# WM1302_915_SPI_without_SX1262_SKY66420_v.net
KiCad netlist of a schematic drawn in EAGLE
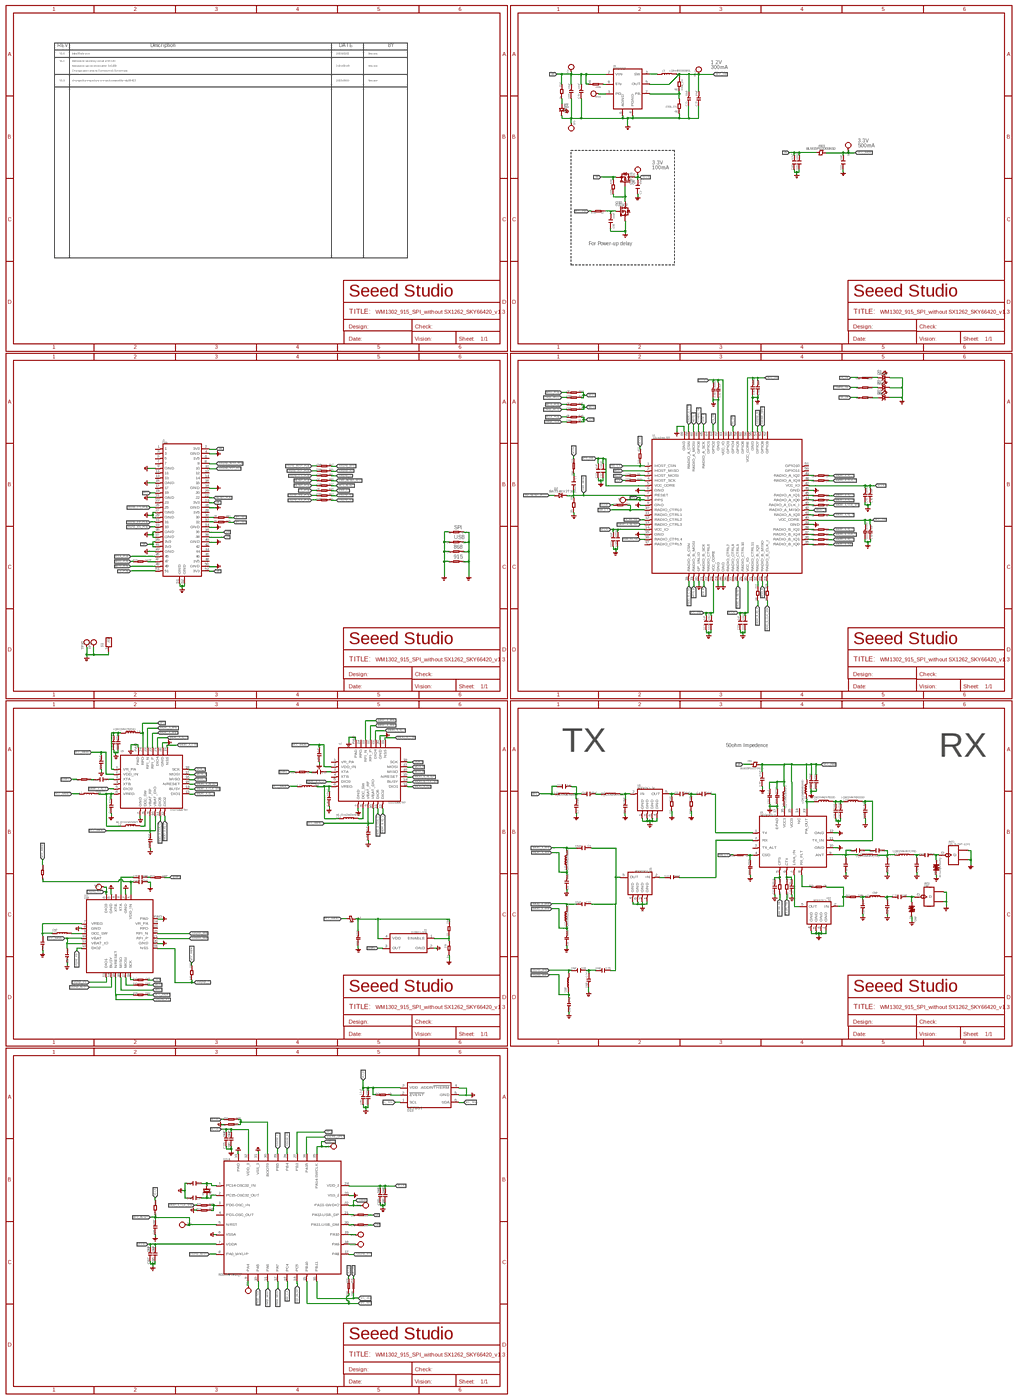
[diagram p0: schematic, sheet 1, overview]
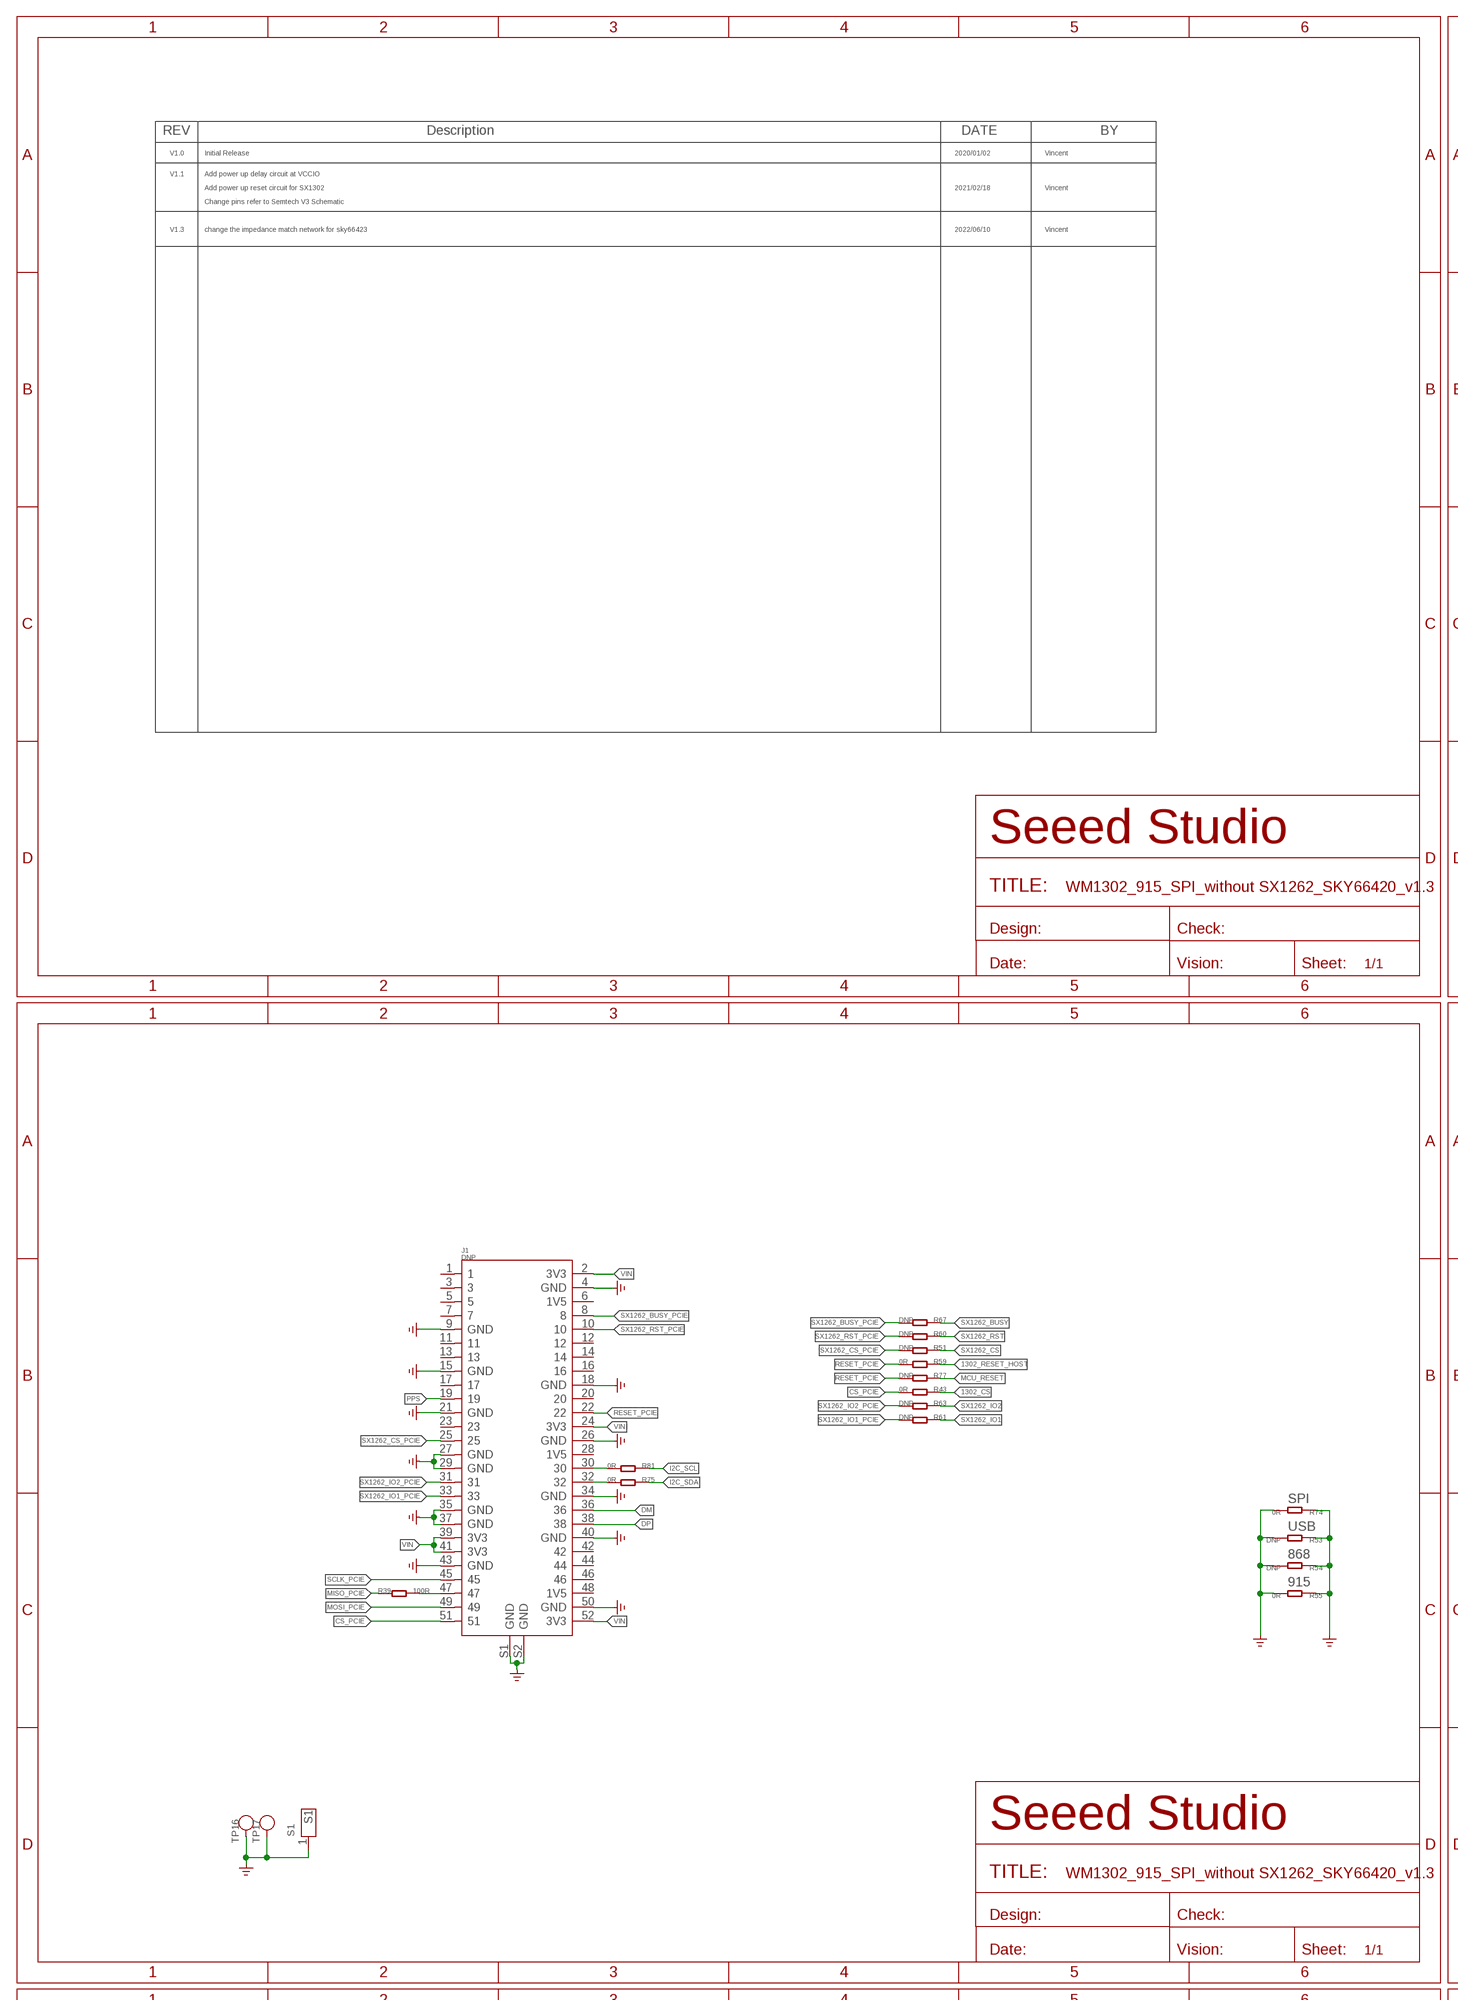
[diagram p1: schematic, sheet 1, part 1 of 4]
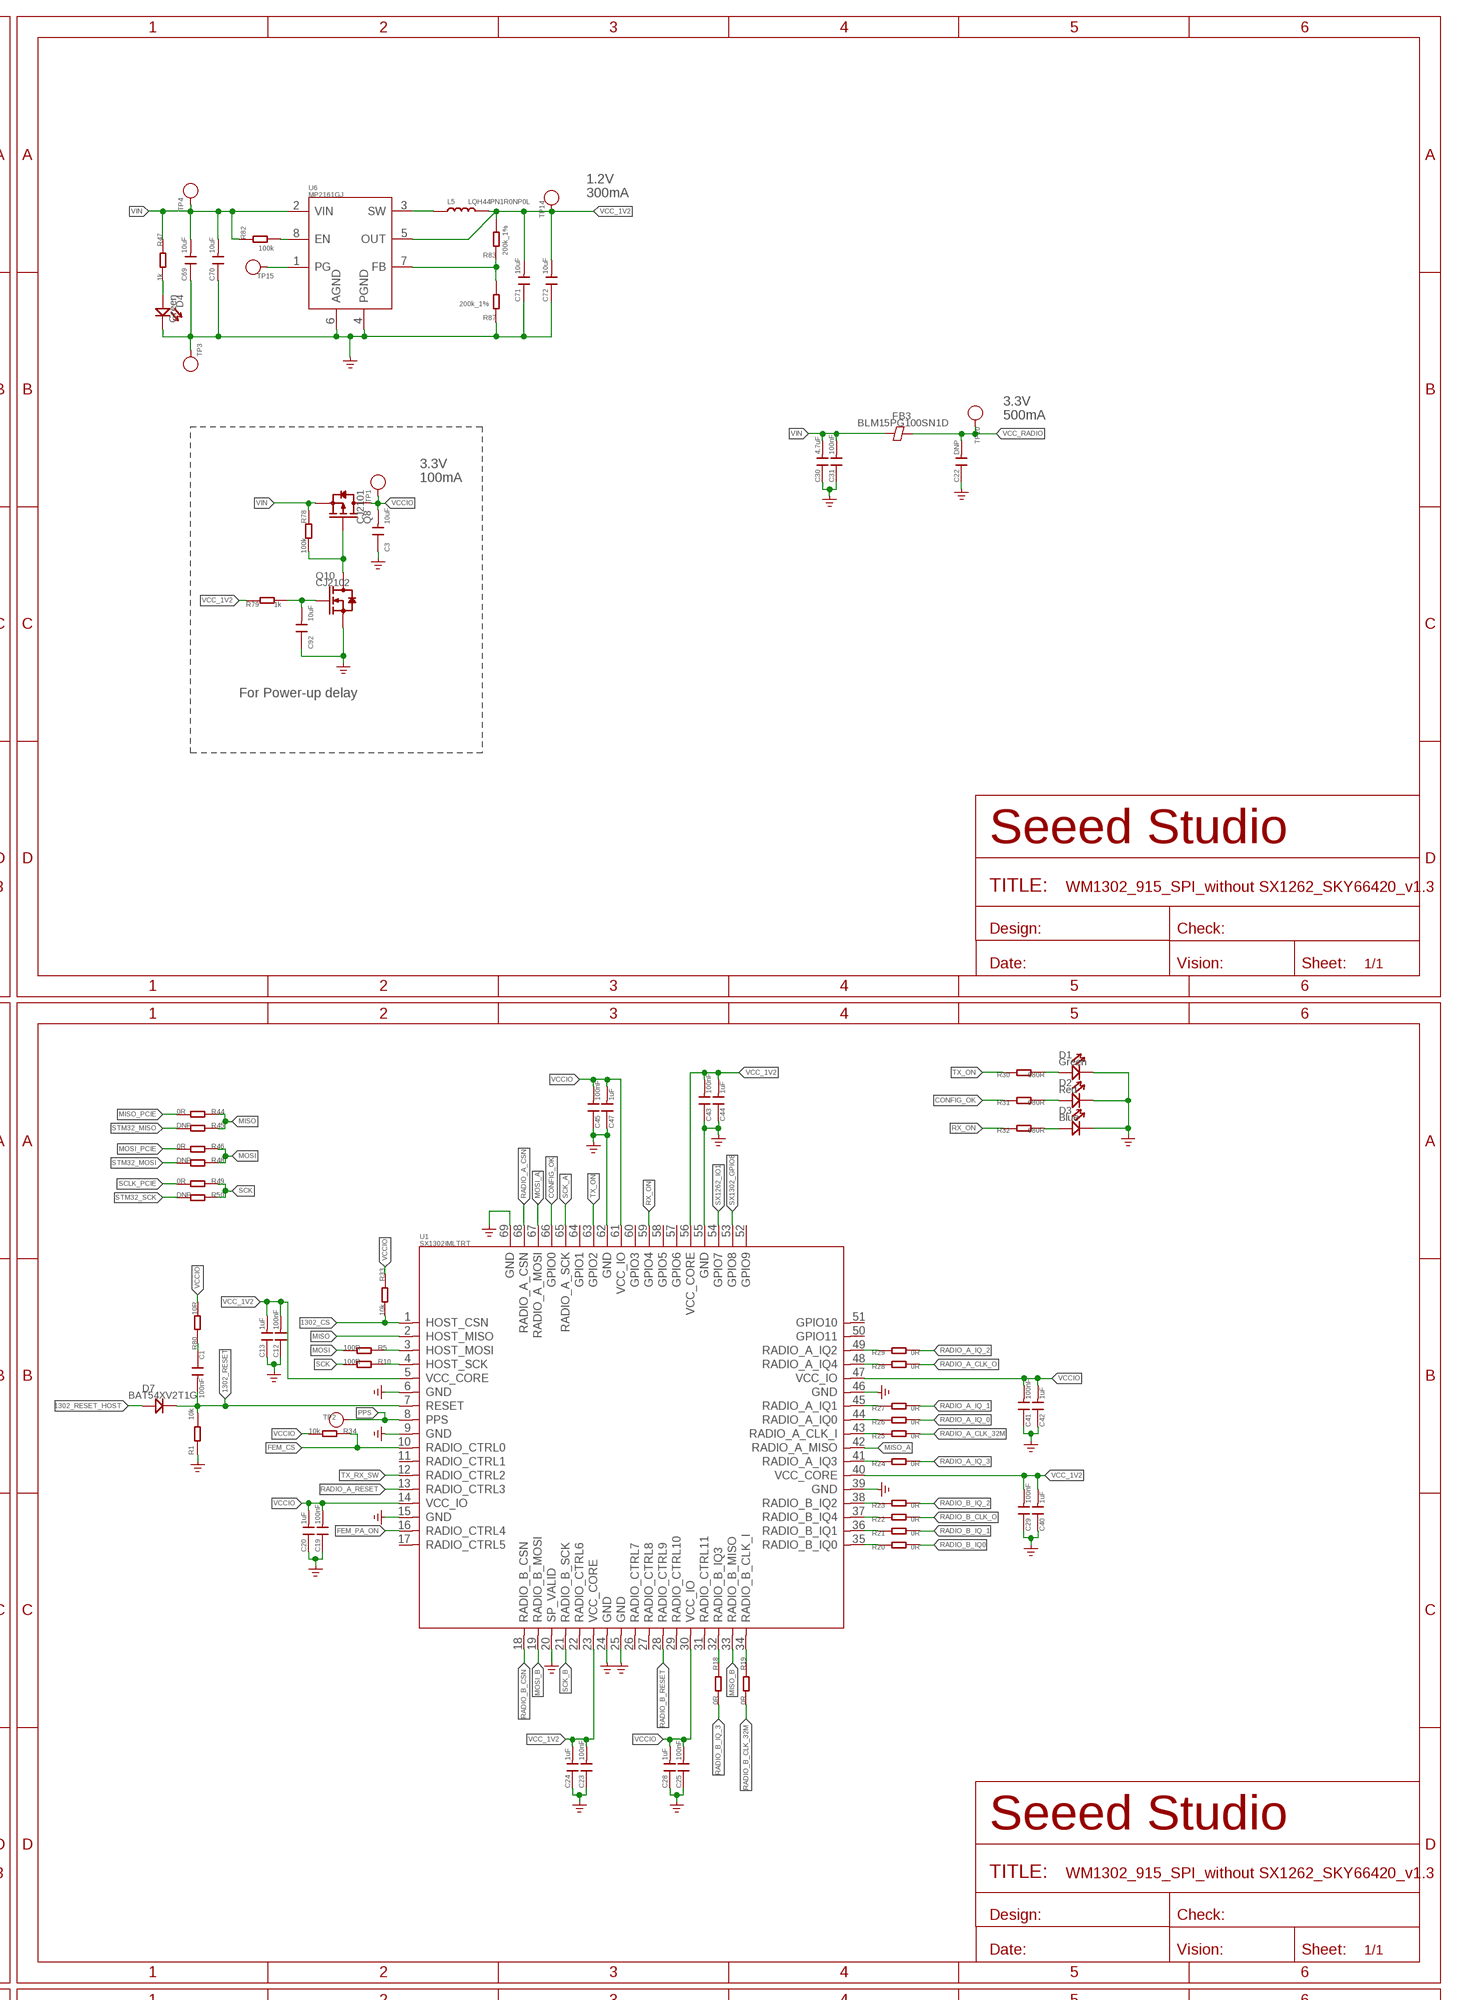
[diagram p2: schematic, sheet 1, part 2 of 4]
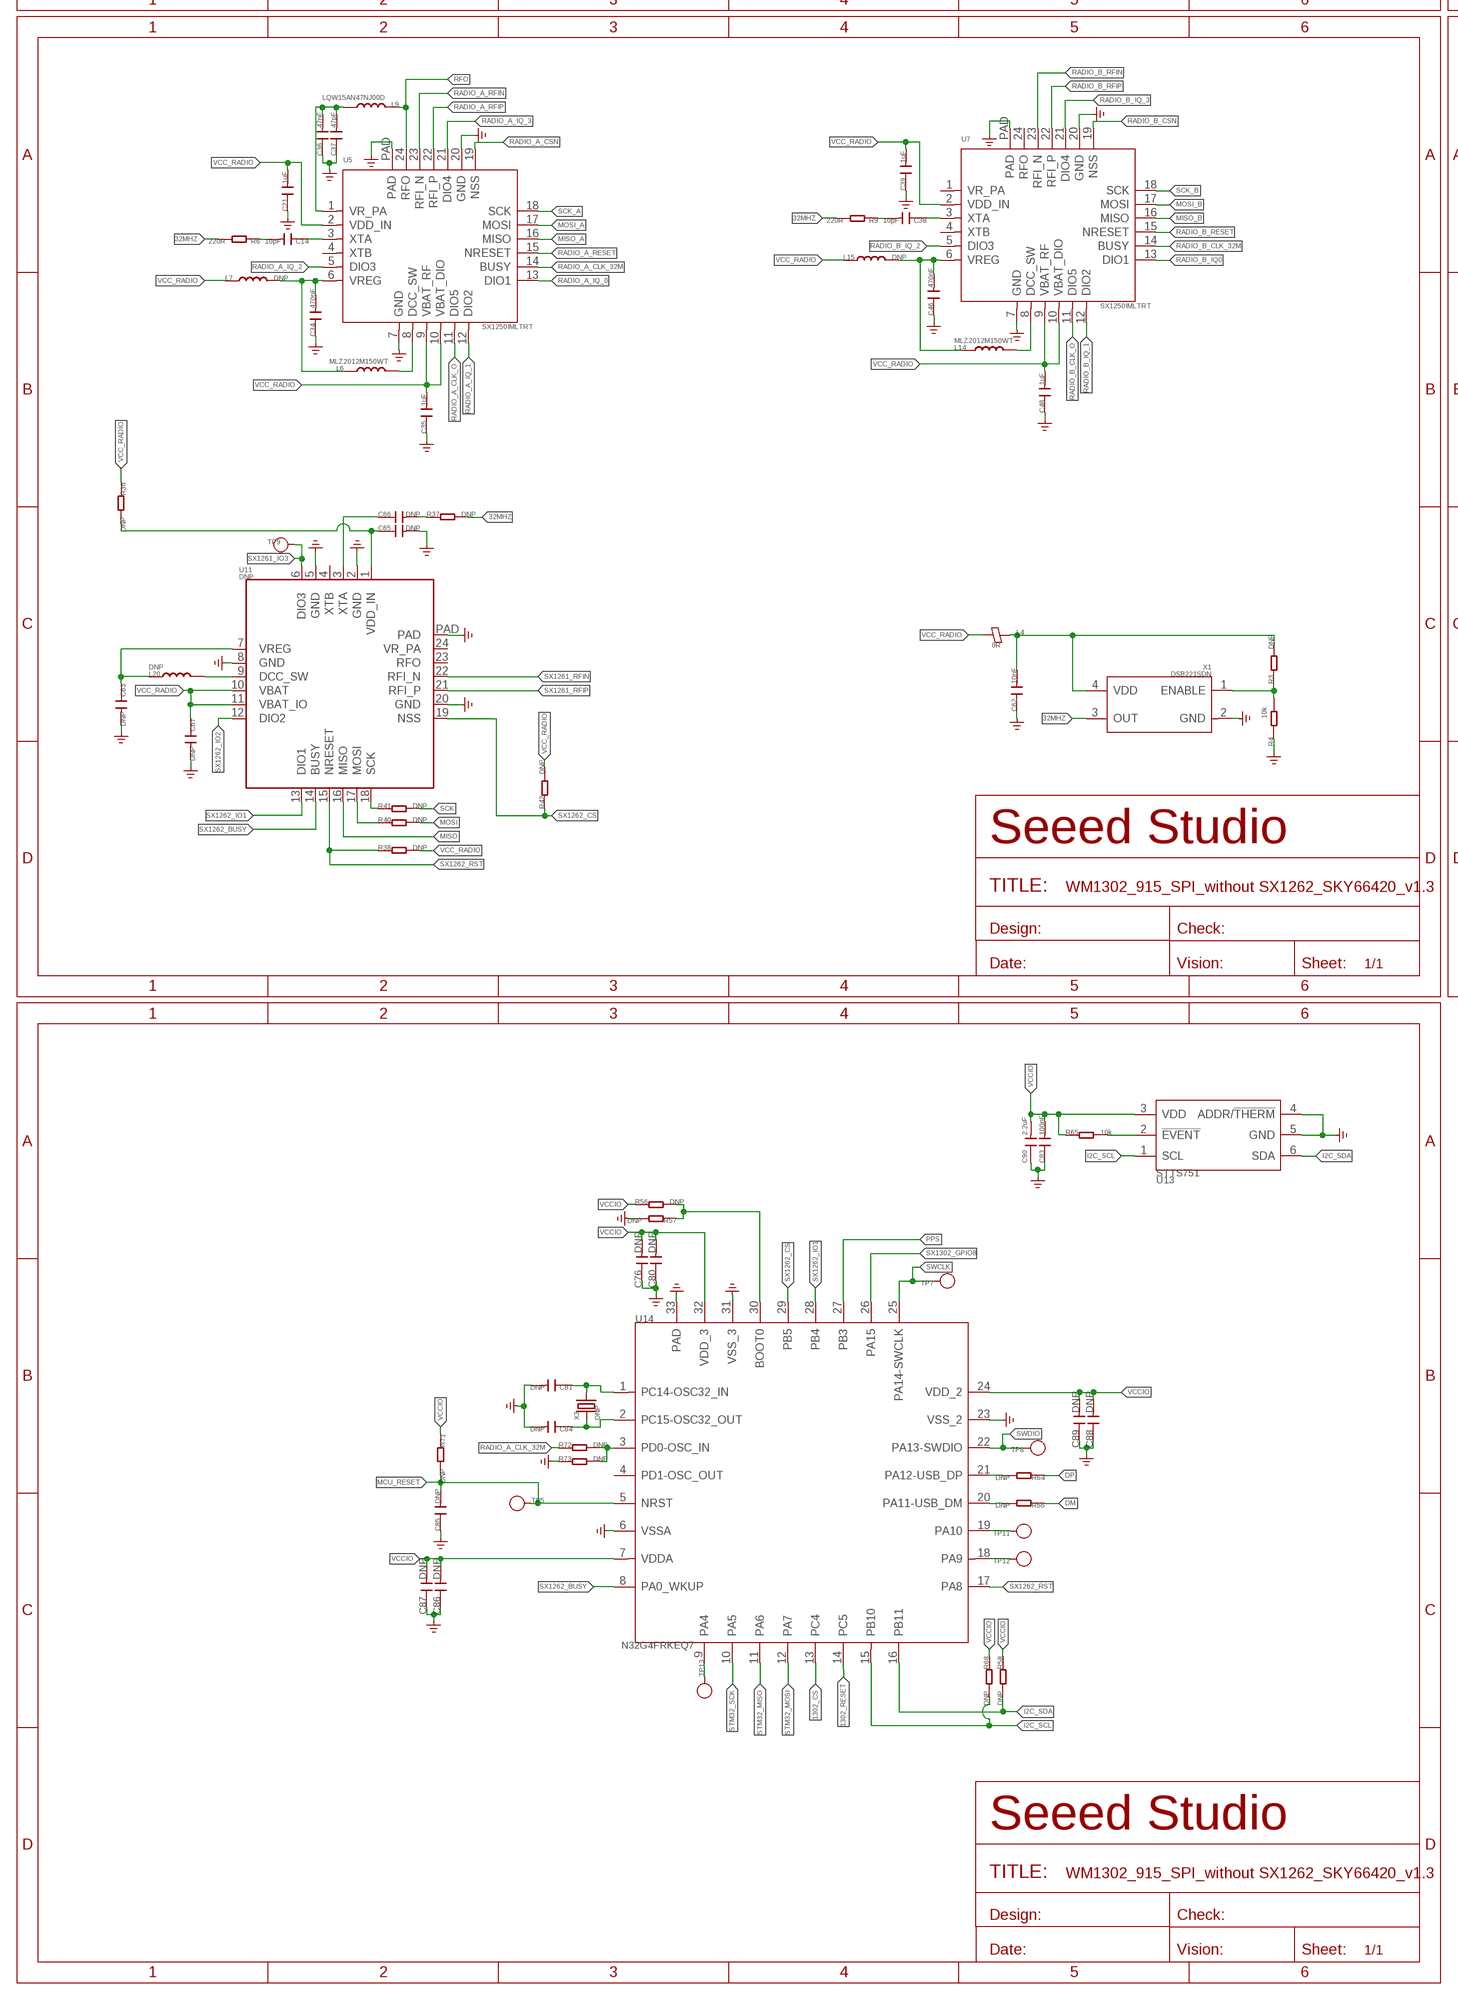
[diagram p3: schematic, sheet 1, part 3 of 4]
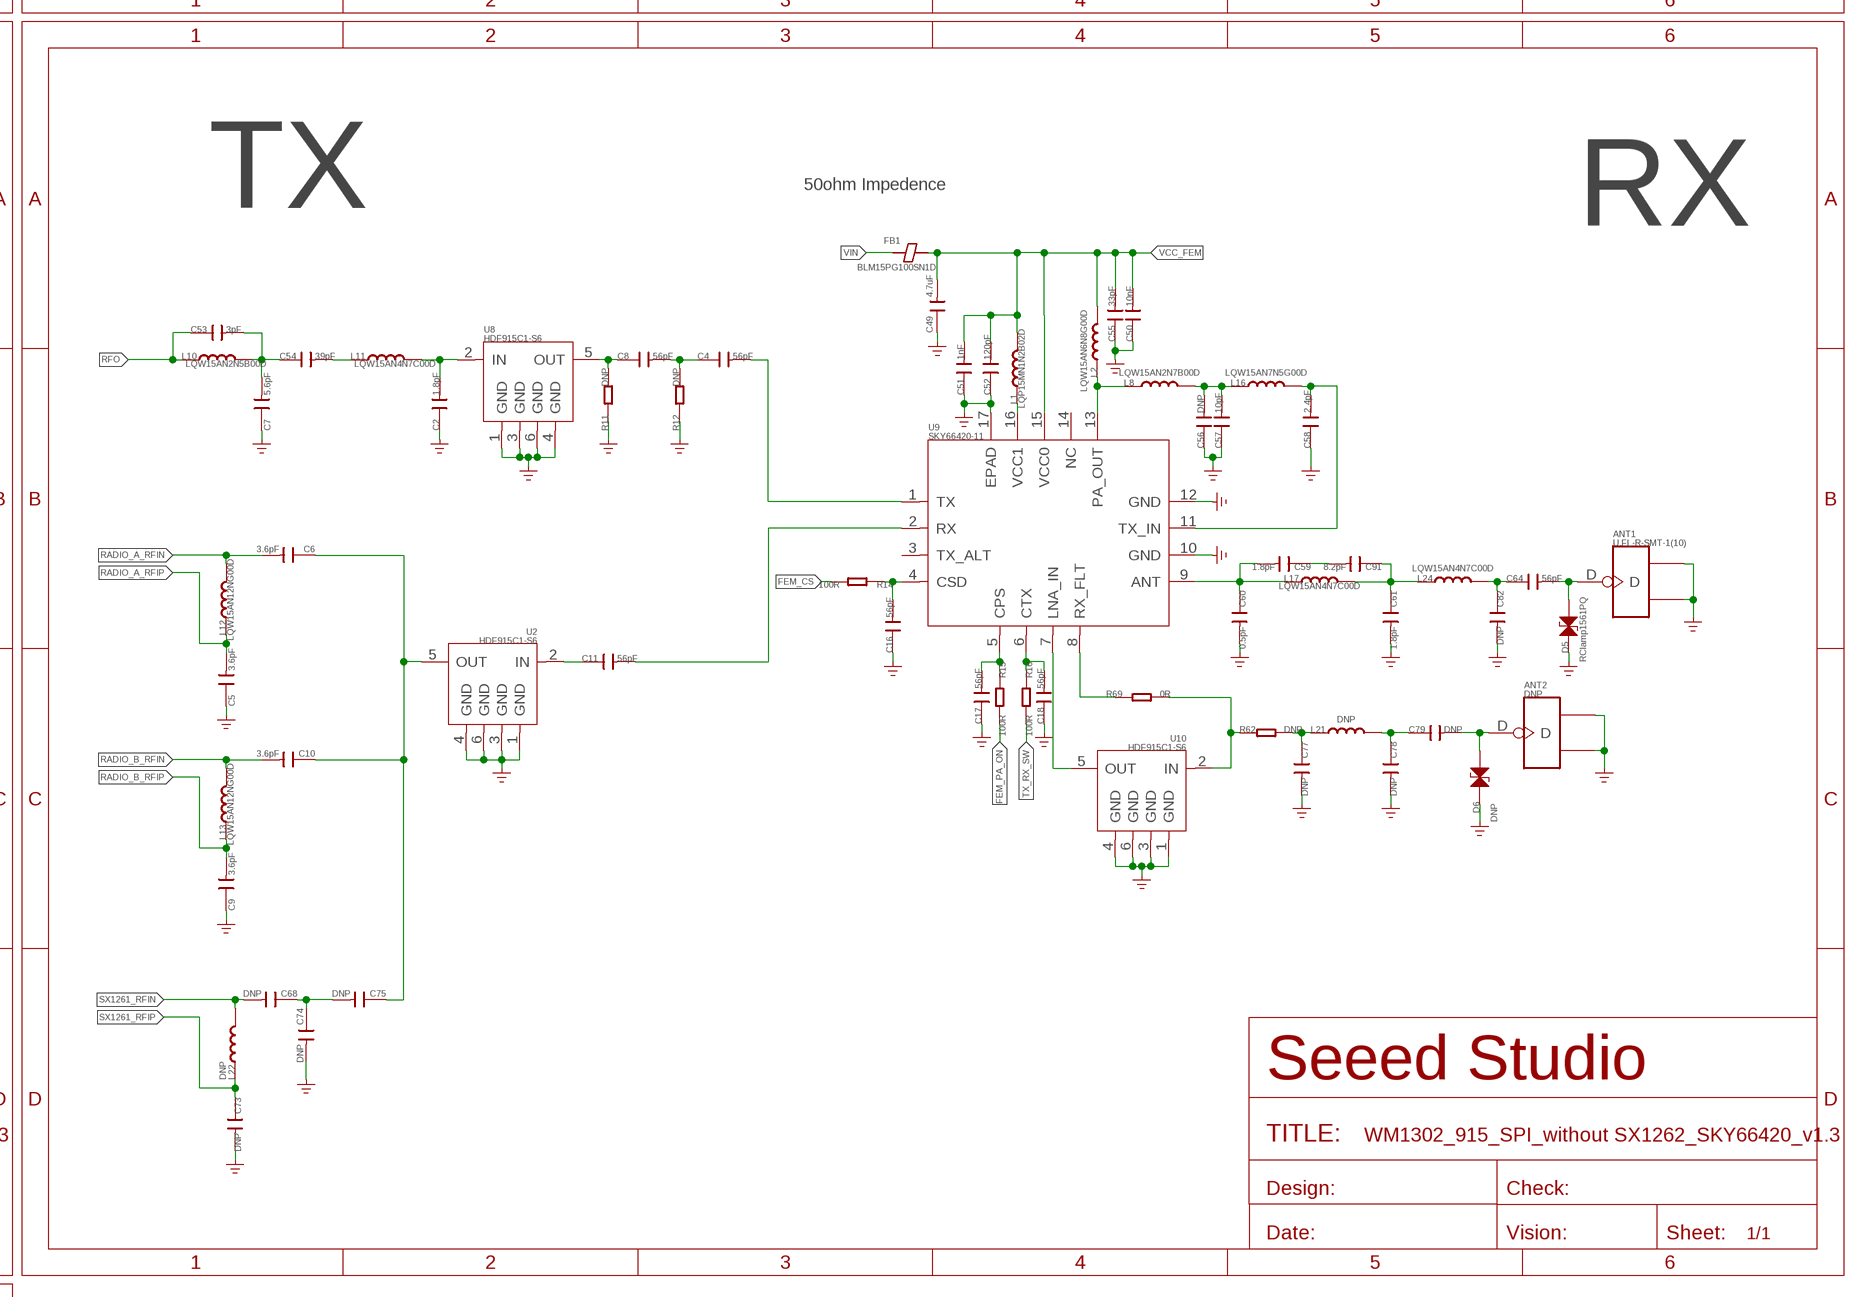
[diagram p4: schematic, sheet 1, part 4 of 4]

(export (version "E")
  (design (tool "Eeschema 10.0.6"))
  (components
    (comp (ref "ANT1")
      (value "U.FL-R-SMT-1(10)")
      (footprint "eagle-import:U-FL3P-SMD-2.6X2.6X1.0MM")
      (fields (field (name "SPICEPREFIX") "J"))
      (libsource (lib "eagle-import") (part "ANTENNA-U-FL-320110048"))
    )
    (comp (ref "ANT2")
      (value "DNP")
      (footprint "eagle-import:U-FL3P-SMD-2.6X2.6X1.0MM")
      (fields (field (name "SPICEPREFIX") "J"))
      (libsource (lib "eagle-import") (part "ANTENNA-U-FL-320110048"))
    )
    (comp (ref "C1")
      (value "100nF")
      (footprint "eagle-import:C0402")
      (libsource (lib "eagle-import") (part "C-0402"))
    )
    (comp (ref "C2")
      (value "1.8pF")
      (footprint "eagle-import:C0402")
      (libsource (lib "eagle-import") (part "C-0402"))
    )
    (comp (ref "C3")
      (value "10uF")
      (footprint "eagle-import:C0603")
      (libsource (lib "eagle-import") (part "C-0603"))
    )
    (comp (ref "C4")
      (value "56pF")
      (footprint "eagle-import:C0402")
      (libsource (lib "eagle-import") (part "C-0402"))
    )
    (comp (ref "C5")
      (value "3.6pF")
      (footprint "eagle-import:C0402")
      (libsource (lib "eagle-import") (part "C-0402"))
    )
    (comp (ref "C6")
      (value "3.6pF")
      (footprint "eagle-import:C0402")
      (libsource (lib "eagle-import") (part "C-0402"))
    )
    (comp (ref "C7")
      (value "5.6pF")
      (footprint "eagle-import:C0402")
      (libsource (lib "eagle-import") (part "C-0402"))
    )
    (comp (ref "C8")
      (value "56pF")
      (footprint "eagle-import:C0402")
      (libsource (lib "eagle-import") (part "C-0402"))
    )
    (comp (ref "C9")
      (value "3.6pF")
      (footprint "eagle-import:C0402")
      (libsource (lib "eagle-import") (part "C-0402"))
    )
    (comp (ref "C10")
      (value "3.6pF")
      (footprint "eagle-import:C0402")
      (libsource (lib "eagle-import") (part "C-0402"))
    )
    (comp (ref "C11")
      (value "56pF")
      (footprint "eagle-import:C0402")
      (libsource (lib "eagle-import") (part "C-0402"))
    )
    (comp (ref "C12")
      (value "100nF")
      (footprint "eagle-import:C0402")
      (libsource (lib "eagle-import") (part "C-0402"))
    )
    (comp (ref "C13")
      (value "1uF")
      (footprint "eagle-import:C0402")
      (libsource (lib "eagle-import") (part "C-0402"))
    )
    (comp (ref "C14")
      (value "10pF")
      (footprint "eagle-import:C0402")
      (libsource (lib "eagle-import") (part "C-0402"))
    )
    (comp (ref "C16")
      (value "56pF")
      (footprint "eagle-import:C0402")
      (libsource (lib "eagle-import") (part "C-0402"))
    )
    (comp (ref "C17")
      (value "56pF")
      (footprint "eagle-import:C0402")
      (libsource (lib "eagle-import") (part "C-0402"))
    )
    (comp (ref "C18")
      (value "56pF")
      (footprint "eagle-import:C0402")
      (libsource (lib "eagle-import") (part "C-0402"))
    )
    (comp (ref "C19")
      (value "100nF")
      (footprint "eagle-import:C0402")
      (libsource (lib "eagle-import") (part "C-0402"))
    )
    (comp (ref "C20")
      (value "1uF")
      (footprint "eagle-import:C0402")
      (libsource (lib "eagle-import") (part "C-0402"))
    )
    (comp (ref "C21")
      (value "1uF")
      (footprint "eagle-import:C0402")
      (libsource (lib "eagle-import") (part "C-0402"))
    )
    (comp (ref "C22")
      (value "DNP")
      (footprint "eagle-import:C0402")
      (libsource (lib "eagle-import") (part "C-0402"))
    )
    (comp (ref "C23")
      (value "100nF")
      (footprint "eagle-import:C0402")
      (libsource (lib "eagle-import") (part "C-0402"))
    )
    (comp (ref "C24")
      (value "1uF")
      (footprint "eagle-import:C0402")
      (libsource (lib "eagle-import") (part "C-0402"))
    )
    (comp (ref "C25")
      (value "100nF")
      (footprint "eagle-import:C0402")
      (libsource (lib "eagle-import") (part "C-0402"))
    )
    (comp (ref "C28")
      (value "1uF")
      (footprint "eagle-import:C0402")
      (libsource (lib "eagle-import") (part "C-0402"))
    )
    (comp (ref "C29")
      (value "100nF")
      (footprint "eagle-import:C0402")
      (libsource (lib "eagle-import") (part "C-0402"))
    )
    (comp (ref "C30")
      (value "4.7uF")
      (footprint "eagle-import:C0603")
      (libsource (lib "eagle-import") (part "C-0603"))
    )
    (comp (ref "C31")
      (value "100nF")
      (footprint "eagle-import:C0402")
      (libsource (lib "eagle-import") (part "C-0402"))
    )
    (comp (ref "C34")
      (value "470nF")
      (footprint "eagle-import:C0402")
      (libsource (lib "eagle-import") (part "C-0402"))
    )
    (comp (ref "C35")
      (value "1uF")
      (footprint "eagle-import:C0402")
      (libsource (lib "eagle-import") (part "C-0402"))
    )
    (comp (ref "C36")
      (value "47nF")
      (footprint "eagle-import:C0402")
      (libsource (lib "eagle-import") (part "C-0402"))
    )
    (comp (ref "C37")
      (value "47pF")
      (footprint "eagle-import:C0402")
      (libsource (lib "eagle-import") (part "C-0402"))
    )
    (comp (ref "C38")
      (value "10pF")
      (footprint "eagle-import:C0402")
      (libsource (lib "eagle-import") (part "C-0402"))
    )
    (comp (ref "C39")
      (value "1uF")
      (footprint "eagle-import:C0402")
      (libsource (lib "eagle-import") (part "C-0402"))
    )
    (comp (ref "C40")
      (value "1uF")
      (footprint "eagle-import:C0402")
      (libsource (lib "eagle-import") (part "C-0402"))
    )
    (comp (ref "C41")
      (value "100nF")
      (footprint "eagle-import:C0402")
      (libsource (lib "eagle-import") (part "C-0402"))
    )
    (comp (ref "C42")
      (value "1uF")
      (footprint "eagle-import:C0402")
      (libsource (lib "eagle-import") (part "C-0402"))
    )
    (comp (ref "C43")
      (value "100nF")
      (footprint "eagle-import:C0402")
      (libsource (lib "eagle-import") (part "C-0402"))
    )
    (comp (ref "C44")
      (value "1uF")
      (footprint "eagle-import:C0402")
      (libsource (lib "eagle-import") (part "C-0402"))
    )
    (comp (ref "C45")
      (value "100nF")
      (footprint "eagle-import:C0402")
      (libsource (lib "eagle-import") (part "C-0402"))
    )
    (comp (ref "C46")
      (value "470nF")
      (footprint "eagle-import:C0402")
      (libsource (lib "eagle-import") (part "C-0402"))
    )
    (comp (ref "C47")
      (value "1uF")
      (footprint "eagle-import:C0402")
      (libsource (lib "eagle-import") (part "C-0402"))
    )
    (comp (ref "C48")
      (value "1uF")
      (footprint "eagle-import:C0402")
      (libsource (lib "eagle-import") (part "C-0402"))
    )
    (comp (ref "C49")
      (value "4.7uF")
      (footprint "eagle-import:C0603")
      (libsource (lib "eagle-import") (part "C-0603"))
    )
    (comp (ref "C50")
      (value "10nF")
      (footprint "eagle-import:C0402")
      (libsource (lib "eagle-import") (part "C-0402"))
    )
    (comp (ref "C51")
      (value "1nF")
      (footprint "eagle-import:C0402")
      (libsource (lib "eagle-import") (part "C-0402"))
    )
    (comp (ref "C52")
      (value "120pF")
      (footprint "eagle-import:C0402")
      (libsource (lib "eagle-import") (part "C-0402"))
    )
    (comp (ref "C53")
      (value "3pF")
      (footprint "eagle-import:C0402")
      (libsource (lib "eagle-import") (part "C-0402"))
    )
    (comp (ref "C54")
      (value "39pF")
      (footprint "eagle-import:C0402")
      (libsource (lib "eagle-import") (part "C-0402"))
    )
    (comp (ref "C55")
      (value "33pF")
      (footprint "eagle-import:C0402")
      (fields (field (name "SPICEPREFIX") "C"))
      (libsource (lib "eagle-import") (part "C-0402"))
    )
    (comp (ref "C56")
      (value "DNP")
      (footprint "eagle-import:C0402")
      (libsource (lib "eagle-import") (part "C-0402"))
    )
    (comp (ref "C57")
      (value "10pF")
      (footprint "eagle-import:C0402")
      (libsource (lib "eagle-import") (part "C-0402"))
    )
    (comp (ref "C58")
      (value "2.4pF")
      (footprint "eagle-import:C0402")
      (libsource (lib "eagle-import") (part "C-0402"))
    )
    (comp (ref "C59")
      (value "1.8pF")
      (footprint "eagle-import:C0402")
      (libsource (lib "eagle-import") (part "C-0402"))
    )
    (comp (ref "C60")
      (value "0.5pF")
      (footprint "eagle-import:C0402")
      (libsource (lib "eagle-import") (part "C-0402"))
    )
    (comp (ref "C61")
      (value "1.8pF")
      (footprint "eagle-import:C0402")
      (libsource (lib "eagle-import") (part "C-0402"))
    )
    (comp (ref "C62")
      (value "10nF")
      (footprint "eagle-import:C0402")
      (libsource (lib "eagle-import") (part "C-0402"))
    )
    (comp (ref "C63")
      (value "DNP")
      (footprint "eagle-import:C0402")
      (libsource (lib "eagle-import") (part "C-0402"))
    )
    (comp (ref "C64")
      (value "56pF")
      (footprint "eagle-import:C0402")
      (libsource (lib "eagle-import") (part "C-0402"))
    )
    (comp (ref "C65")
      (value "DNP")
      (footprint "eagle-import:C0402")
      (libsource (lib "eagle-import") (part "C-0402"))
    )
    (comp (ref "C66")
      (value "DNP")
      (footprint "eagle-import:C0402")
      (libsource (lib "eagle-import") (part "C-0402"))
    )
    (comp (ref "C67")
      (value "DNP")
      (footprint "eagle-import:C0402")
      (libsource (lib "eagle-import") (part "C-0402"))
    )
    (comp (ref "C68")
      (value "DNP")
      (footprint "eagle-import:C0402")
      (libsource (lib "eagle-import") (part "C-0402"))
    )
    (comp (ref "C69")
      (value "10uF")
      (footprint "eagle-import:C0805")
      (libsource (lib "eagle-import") (part "CAP-0805"))
    )
    (comp (ref "C70")
      (value "10uF")
      (footprint "eagle-import:C0805")
      (libsource (lib "eagle-import") (part "CAP-0805"))
    )
    (comp (ref "C71")
      (value "10uF")
      (footprint "eagle-import:C0805")
      (libsource (lib "eagle-import") (part "CAP-0805"))
    )
    (comp (ref "C72")
      (value "10uF")
      (footprint "eagle-import:C0805")
      (libsource (lib "eagle-import") (part "CAP-0805"))
    )
    (comp (ref "C73")
      (value "DNP")
      (footprint "eagle-import:C0402")
      (libsource (lib "eagle-import") (part "C-0402"))
    )
    (comp (ref "C74")
      (value "DNP")
      (footprint "eagle-import:C0402")
      (libsource (lib "eagle-import") (part "C-0402"))
    )
    (comp (ref "C75")
      (value "DNP")
      (footprint "eagle-import:C0402")
      (libsource (lib "eagle-import") (part "C-0402"))
    )
    (comp (ref "C76")
      (value "DNP")
      (footprint "eagle-import:C0402")
      (libsource (lib "eagle-import") (part "C-0402"))
    )
    (comp (ref "C77")
      (value "DNP")
      (footprint "eagle-import:C0402")
      (libsource (lib "eagle-import") (part "C-0402"))
    )
    (comp (ref "C78")
      (value "DNP")
      (footprint "eagle-import:C0402")
      (libsource (lib "eagle-import") (part "C-0402"))
    )
    (comp (ref "C79")
      (value "DNP")
      (footprint "eagle-import:C0402")
      (libsource (lib "eagle-import") (part "C-0402"))
    )
    (comp (ref "C80")
      (value "DNP")
      (footprint "eagle-import:C0402")
      (libsource (lib "eagle-import") (part "C-0402"))
    )
    (comp (ref "C81")
      (value "DNP")
      (footprint "eagle-import:C0402")
      (libsource (lib "eagle-import") (part "C-0402"))
    )
    (comp (ref "C82")
      (value "DNP")
      (footprint "eagle-import:C0402")
      (libsource (lib "eagle-import") (part "C-0402"))
    )
    (comp (ref "C83")
      (value "100nF")
      (footprint "eagle-import:C0402")
      (libsource (lib "eagle-import") (part "C-0402"))
    )
    (comp (ref "C84")
      (value "DNP")
      (footprint "eagle-import:C0402")
      (libsource (lib "eagle-import") (part "C-0402"))
    )
    (comp (ref "C85")
      (value "DNP")
      (footprint "eagle-import:C0402")
      (libsource (lib "eagle-import") (part "C-0402"))
    )
    (comp (ref "C86")
      (value "DNP")
      (footprint "eagle-import:C0402")
      (libsource (lib "eagle-import") (part "C-0402"))
    )
    (comp (ref "C87")
      (value "DNP")
      (footprint "eagle-import:C0402")
      (libsource (lib "eagle-import") (part "C-0402"))
    )
    (comp (ref "C88")
      (value "DNP")
      (footprint "eagle-import:C0402")
      (libsource (lib "eagle-import") (part "C-0402"))
    )
    (comp (ref "C89")
      (value "DNP")
      (footprint "eagle-import:C0402")
      (libsource (lib "eagle-import") (part "C-0402"))
    )
    (comp (ref "C90")
      (value "2.2uF")
      (footprint "eagle-import:C0603")
      (libsource (lib "eagle-import") (part "C-0603"))
    )
    (comp (ref "C91")
      (value "8.2pF")
      (footprint "eagle-import:C0402")
      (libsource (lib "eagle-import") (part "C-0402"))
    )
    (comp (ref "C92")
      (value "10uF")
      (footprint "eagle-import:C0603")
      (libsource (lib "eagle-import") (part "C-0603"))
    )
    (comp (ref "D1")
      (value "Green")
      (footprint "eagle-import:LED-0402")
      (libsource (lib "eagle-import") (part "LED-0402"))
    )
    (comp (ref "D2")
      (value "Red")
      (footprint "eagle-import:LED-0402")
      (libsource (lib "eagle-import") (part "LED-0402"))
    )
    (comp (ref "D3")
      (value "Blue")
      (footprint "eagle-import:LED-0402")
      (libsource (lib "eagle-import") (part "LED-0402"))
    )
    (comp (ref "D4")
      (value "Green")
      (footprint "eagle-import:LED-0402")
      (libsource (lib "eagle-import") (part "LED-0402"))
    )
    (comp (ref "D5")
      (value "RClamp1561PQ")
      (footprint "eagle-import:ESD-0402")
      (fields (field (name "SPICEPREFIX") "D"))
      (libsource (lib "eagle-import") (part "D-ESD-2P-DOUBLE-0402"))
    )
    (comp (ref "D6")
      (value "DNP")
      (footprint "eagle-import:ESD-0402")
      (libsource (lib "eagle-import") (part "D-ESD-2P-DOUBLE-0402"))
    )
    (comp (ref "D7")
      (value "BAT54XV2T1G")
      (footprint "eagle-import:SOD-523")
      (libsource (lib "eagle-import") (part "DIODE'0603'"))
    )
    (comp (ref "FB1")
      (value "BLM15PG100SN1D")
      (footprint "eagle-import:F0402")
      (libsource (lib "eagle-import") (part "FERRITE-BEAD-0402"))
    )
    (comp (ref "FB3")
      (value "BLM15PG100SN1D")
      (footprint "eagle-import:F0402")
      (libsource (lib "eagle-import") (part "FERRITE-BEAD-0402"))
    )
    (comp (ref "J1")
      (value "DNP")
      (footprint "eagle-import:PCIE52P-0.8-50.95X30MM")
      (libsource (lib "eagle-import") (part "MOUDLE-FULL-MINI-PCIE"))
    )
    (comp (ref "L1")
      (value "LQP15MN1N2B02D")
      (footprint "eagle-import:L0402")
      (libsource (lib "eagle-import") (part "L-0402"))
    )
    (comp (ref "L2")
      (value "LQW15AN6N8G00D")
      (footprint "eagle-import:L0402")
      (libsource (lib "eagle-import") (part "L-0402"))
    )
    (comp (ref "L4")
      (value "0R")
      (footprint "eagle-import:F0603")
      (libsource (lib "eagle-import") (part "FERRITE-BEAD-0603"))
    )
    (comp (ref "L5")
      (value "LQH44PN1R0NP0L")
      (footprint "eagle-import:L4.4X3.0MM")
      (libsource (lib "eagle-import") (part "INDUCTOR-4430"))
    )
    (comp (ref "L6")
      (value "MLZ2012M150WT")
      (footprint "eagle-import:L202012")
      (libsource (lib "eagle-import") (part "INDUCTOR-SPH202012"))
    )
    (comp (ref "L7")
      (value "DNP")
      (footprint "eagle-import:L0402")
      (libsource (lib "eagle-import") (part "L-0402"))
    )
    (comp (ref "L8")
      (value "LQW15AN2N7B00D")
      (footprint "eagle-import:L0402")
      (libsource (lib "eagle-import") (part "L-0402"))
    )
    (comp (ref "L9")
      (value "LQW15AN47NJ00D")
      (footprint "eagle-import:L0402")
      (libsource (lib "eagle-import") (part "L-0402"))
    )
    (comp (ref "L10")
      (value "LQW15AN2N5B00D")
      (footprint "eagle-import:L0402")
      (libsource (lib "eagle-import") (part "L-0402"))
    )
    (comp (ref "L11")
      (value "LQW15AN4N7C00D")
      (footprint "eagle-import:L0402")
      (libsource (lib "eagle-import") (part "L-0402"))
    )
    (comp (ref "L12")
      (value "LQW15AN12NG00D")
      (footprint "eagle-import:L0402")
      (libsource (lib "eagle-import") (part "L-0402"))
    )
    (comp (ref "L13")
      (value "LQW15AN12NG00D")
      (footprint "eagle-import:L0402")
      (libsource (lib "eagle-import") (part "L-0402"))
    )
    (comp (ref "L14")
      (value "MLZ2012M150WT")
      (footprint "eagle-import:L202012")
      (libsource (lib "eagle-import") (part "INDUCTOR-SPH202012"))
    )
    (comp (ref "L15")
      (value "DNP")
      (footprint "eagle-import:L0402")
      (libsource (lib "eagle-import") (part "L-0402"))
    )
    (comp (ref "L16")
      (value "LQW15AN7N5G00D")
      (footprint "eagle-import:L0402")
      (libsource (lib "eagle-import") (part "L-0402"))
    )
    (comp (ref "L17")
      (value "LQW15AN4N7C00D")
      (footprint "eagle-import:L0402")
      (libsource (lib "eagle-import") (part "L-0402"))
    )
    (comp (ref "L20")
      (value "DNP")
      (footprint "eagle-import:L202012")
      (libsource (lib "eagle-import") (part "INDUCTOR-SPH202012"))
    )
    (comp (ref "L21")
      (value "DNP")
      (footprint "eagle-import:L0402")
      (libsource (lib "eagle-import") (part "L-0402"))
    )
    (comp (ref "L22")
      (value "DNP")
      (footprint "eagle-import:L0402")
      (libsource (lib "eagle-import") (part "L-0402"))
    )
    (comp (ref "L24")
      (value "LQW15AN4N7C00D")
      (footprint "eagle-import:L0402")
      (libsource (lib "eagle-import") (part "L-0402"))
    )
    (comp (ref "Q8")
      (value "CJ2101")
      (footprint "eagle-import:SOT-323")
      (libsource (lib "eagle-import") (part "MOSFET-P-SOT323"))
    )
    (comp (ref "Q10")
      (value "CJ2102")
      (footprint "eagle-import:SOT-323")
      (libsource (lib "eagle-import") (part "MOSFET-N-SI1304BDL"))
    )
    (comp (ref "R1")
      (value "10k")
      (footprint "eagle-import:R0402")
      (libsource (lib "eagle-import") (part "R-0402"))
    )
    (comp (ref "R3")
      (value "DNP")
      (footprint "eagle-import:R0402")
      (libsource (lib "eagle-import") (part "R-0402"))
    )
    (comp (ref "R4")
      (value "10k")
      (footprint "eagle-import:R0402")
      (libsource (lib "eagle-import") (part "R-0402"))
    )
    (comp (ref "R5")
      (value "100R")
      (footprint "eagle-import:R0402")
      (libsource (lib "eagle-import") (part "R-0402"))
    )
    (comp (ref "R6")
      (value "220R")
      (footprint "eagle-import:R0402")
      (libsource (lib "eagle-import") (part "R-0402"))
    )
    (comp (ref "R9")
      (value "220R")
      (footprint "eagle-import:R0402")
      (libsource (lib "eagle-import") (part "R-0402"))
    )
    (comp (ref "R10")
      (value "100R")
      (footprint "eagle-import:R0402")
      (libsource (lib "eagle-import") (part "R-0402"))
    )
    (comp (ref "R11")
      (value "DNP")
      (footprint "eagle-import:R0402")
      (libsource (lib "eagle-import") (part "R-0402"))
    )
    (comp (ref "R12")
      (value "DNP")
      (footprint "eagle-import:R0402")
      (libsource (lib "eagle-import") (part "R-0402"))
    )
    (comp (ref "R14")
      (value "100R")
      (footprint "eagle-import:R0402")
      (libsource (lib "eagle-import") (part "R-0402"))
    )
    (comp (ref "R15")
      (value "100R")
      (footprint "eagle-import:R0402")
      (libsource (lib "eagle-import") (part "R-0402"))
    )
    (comp (ref "R16")
      (value "100R")
      (footprint "eagle-import:R0402")
      (libsource (lib "eagle-import") (part "R-0402"))
    )
    (comp (ref "R18")
      (value "0R")
      (footprint "eagle-import:R0402")
      (libsource (lib "eagle-import") (part "R-0402"))
    )
    (comp (ref "R19")
      (value "0R")
      (footprint "eagle-import:R0402")
      (libsource (lib "eagle-import") (part "R-0402"))
    )
    (comp (ref "R20")
      (value "0R")
      (footprint "eagle-import:R0402")
      (libsource (lib "eagle-import") (part "R-0402"))
    )
    (comp (ref "R21")
      (value "0R")
      (footprint "eagle-import:R0402")
      (libsource (lib "eagle-import") (part "R-0402"))
    )
    (comp (ref "R22")
      (value "0R")
      (footprint "eagle-import:R0402")
      (libsource (lib "eagle-import") (part "R-0402"))
    )
    (comp (ref "R23")
      (value "0R")
      (footprint "eagle-import:R0402")
      (libsource (lib "eagle-import") (part "R-0402"))
    )
    (comp (ref "R24")
      (value "0R")
      (footprint "eagle-import:R0402")
      (libsource (lib "eagle-import") (part "R-0402"))
    )
    (comp (ref "R25")
      (value "0R")
      (footprint "eagle-import:R0402")
      (libsource (lib "eagle-import") (part "R-0402"))
    )
    (comp (ref "R26")
      (value "0R")
      (footprint "eagle-import:R0402")
      (libsource (lib "eagle-import") (part "R-0402"))
    )
    (comp (ref "R27")
      (value "0R")
      (footprint "eagle-import:R0402")
      (libsource (lib "eagle-import") (part "R-0402"))
    )
    (comp (ref "R28")
      (value "0R")
      (footprint "eagle-import:R0402")
      (libsource (lib "eagle-import") (part "R-0402"))
    )
    (comp (ref "R29")
      (value "0R")
      (footprint "eagle-import:R0402")
      (libsource (lib "eagle-import") (part "R-0402"))
    )
    (comp (ref "R30")
      (value "680R")
      (footprint "eagle-import:R0402")
      (libsource (lib "eagle-import") (part "R-0402"))
    )
    (comp (ref "R31")
      (value "680R")
      (footprint "eagle-import:R0402")
      (libsource (lib "eagle-import") (part "R-0402"))
    )
    (comp (ref "R32")
      (value "680R")
      (footprint "eagle-import:R0402")
      (libsource (lib "eagle-import") (part "R-0402"))
    )
    (comp (ref "R33")
      (value "10k")
      (footprint "eagle-import:R0402")
      (libsource (lib "eagle-import") (part "R-0402"))
    )
    (comp (ref "R34")
      (value "10k")
      (footprint "eagle-import:R0402")
      (libsource (lib "eagle-import") (part "R-0402"))
    )
    (comp (ref "R36")
      (value "DNP")
      (footprint "eagle-import:R0402")
      (libsource (lib "eagle-import") (part "R-0402"))
    )
    (comp (ref "R37")
      (value "DNP")
      (footprint "eagle-import:R0402")
      (libsource (lib "eagle-import") (part "R-0402"))
    )
    (comp (ref "R38")
      (value "DNP")
      (footprint "eagle-import:R0402")
      (libsource (lib "eagle-import") (part "R-0402"))
    )
    (comp (ref "R39")
      (value "100R")
      (footprint "eagle-import:R0402")
      (libsource (lib "eagle-import") (part "R-0402"))
    )
    (comp (ref "R40")
      (value "DNP")
      (footprint "eagle-import:R0402")
      (libsource (lib "eagle-import") (part "R-0402"))
    )
    (comp (ref "R41")
      (value "DNP")
      (footprint "eagle-import:R0402")
      (libsource (lib "eagle-import") (part "R-0402"))
    )
    (comp (ref "R42")
      (value "DNP")
      (footprint "eagle-import:R0402")
      (libsource (lib "eagle-import") (part "R-0402"))
    )
    (comp (ref "R43")
      (value "0R")
      (footprint "eagle-import:R0402")
      (libsource (lib "eagle-import") (part "R-0402"))
    )
    (comp (ref "R44")
      (value "0R")
      (footprint "eagle-import:R0402")
      (libsource (lib "eagle-import") (part "R-0402"))
    )
    (comp (ref "R45")
      (value "DNP")
      (footprint "eagle-import:R0402")
      (libsource (lib "eagle-import") (part "R-0402"))
    )
    (comp (ref "R46")
      (value "0R")
      (footprint "eagle-import:R0402")
      (libsource (lib "eagle-import") (part "R-0402"))
    )
    (comp (ref "R47")
      (value "1k")
      (footprint "eagle-import:R0402")
      (libsource (lib "eagle-import") (part "R-0402"))
    )
    (comp (ref "R48")
      (value "DNP")
      (footprint "eagle-import:R0402")
      (libsource (lib "eagle-import") (part "R-0402"))
    )
    (comp (ref "R49")
      (value "0R")
      (footprint "eagle-import:R0402")
      (libsource (lib "eagle-import") (part "R-0402"))
    )
    (comp (ref "R50")
      (value "DNP")
      (footprint "eagle-import:R0402")
      (libsource (lib "eagle-import") (part "R-0402"))
    )
    (comp (ref "R51")
      (value "DNP")
      (footprint "eagle-import:R0402")
      (libsource (lib "eagle-import") (part "R-0402"))
    )
    (comp (ref "R53")
      (value "DNP")
      (footprint "eagle-import:R0402")
      (libsource (lib "eagle-import") (part "R-0402"))
    )
    (comp (ref "R54")
      (value "DNP")
      (footprint "eagle-import:R0402")
      (libsource (lib "eagle-import") (part "R-0402"))
    )
    (comp (ref "R55")
      (value "0R")
      (footprint "eagle-import:R0402")
      (libsource (lib "eagle-import") (part "R-0402"))
    )
    (comp (ref "R56")
      (value "DNP")
      (footprint "eagle-import:R0402")
      (libsource (lib "eagle-import") (part "R-0402"))
    )
    (comp (ref "R57")
      (value "DNP")
      (footprint "eagle-import:R0402")
      (libsource (lib "eagle-import") (part "R-0402"))
    )
    (comp (ref "R58")
      (value "DNP")
      (footprint "eagle-import:R0402")
      (libsource (lib "eagle-import") (part "R-0402"))
    )
    (comp (ref "R59")
      (value "0R")
      (footprint "eagle-import:R0402")
      (libsource (lib "eagle-import") (part "R-0402"))
    )
    (comp (ref "R60")
      (value "DNP")
      (footprint "eagle-import:R0402")
      (libsource (lib "eagle-import") (part "R-0402"))
    )
    (comp (ref "R61")
      (value "DNP")
      (footprint "eagle-import:R0402")
      (libsource (lib "eagle-import") (part "R-0402"))
    )
    (comp (ref "R62")
      (value "DNP")
      (footprint "eagle-import:R0402")
      (libsource (lib "eagle-import") (part "R-0402"))
    )
    (comp (ref "R63")
      (value "DNP")
      (footprint "eagle-import:R0402")
      (libsource (lib "eagle-import") (part "R-0402"))
    )
    (comp (ref "R64")
      (value "DNP")
      (footprint "eagle-import:R0402")
      (libsource (lib "eagle-import") (part "R-0402"))
    )
    (comp (ref "R65")
      (value "10k")
      (footprint "eagle-import:R0402")
      (libsource (lib "eagle-import") (part "R-0402"))
    )
    (comp (ref "R66")
      (value "DNP")
      (footprint "eagle-import:R0402")
      (libsource (lib "eagle-import") (part "R-0402"))
    )
    (comp (ref "R67")
      (value "DNP")
      (footprint "eagle-import:R0402")
      (libsource (lib "eagle-import") (part "R-0402"))
    )
    (comp (ref "R68")
      (value "DNP")
      (footprint "eagle-import:R0402")
      (libsource (lib "eagle-import") (part "R-0402"))
    )
    (comp (ref "R69")
      (value "0R")
      (footprint "eagle-import:R0402")
      (libsource (lib "eagle-import") (part "R-0402"))
    )
    (comp (ref "R71")
      (value "DNP")
      (footprint "eagle-import:R0402")
      (libsource (lib "eagle-import") (part "R-0402"))
    )
    (comp (ref "R72")
      (value "DNP")
      (footprint "eagle-import:R0402")
      (libsource (lib "eagle-import") (part "R-0402"))
    )
    (comp (ref "R73")
      (value "DNP")
      (footprint "eagle-import:R0402")
      (libsource (lib "eagle-import") (part "R-0402"))
    )
    (comp (ref "R74")
      (value "0R")
      (footprint "eagle-import:R0402")
      (libsource (lib "eagle-import") (part "R-0402"))
    )
    (comp (ref "R75")
      (value "0R")
      (footprint "eagle-import:R0402")
      (libsource (lib "eagle-import") (part "R-0402"))
    )
    (comp (ref "R77")
      (value "DNP")
      (footprint "eagle-import:R0402")
      (libsource (lib "eagle-import") (part "R-0402"))
    )
    (comp (ref "R78")
      (value "100k")
      (footprint "eagle-import:R0402")
      (libsource (lib "eagle-import") (part "R-0402"))
    )
    (comp (ref "R79")
      (value "1k")
      (footprint "eagle-import:R0402")
      (libsource (lib "eagle-import") (part "R-0402"))
    )
    (comp (ref "R80")
      (value "10R")
      (footprint "eagle-import:R0402")
      (libsource (lib "eagle-import") (part "R-0402"))
    )
    (comp (ref "R81")
      (value "0R")
      (footprint "eagle-import:R0402")
      (libsource (lib "eagle-import") (part "R-0402"))
    )
    (comp (ref "R82")
      (value "100k")
      (footprint "eagle-import:R0402")
      (libsource (lib "eagle-import") (part "R-0402"))
    )
    (comp (ref "R83")
      (value "200k_1%")
      (footprint "eagle-import:R0402")
      (libsource (lib "eagle-import") (part "R-0402"))
    )
    (comp (ref "R87")
      (value "200k_1%")
      (footprint "eagle-import:R0402")
      (libsource (lib "eagle-import") (part "R-0402"))
    )
    (comp (ref "S1")
      (value "SHIELD_CLIP-1302")
      (footprint "eagle-import:SHIELD_1302")
      (libsource (lib "eagle-import") (part "SHIELD_CLIP-1302"))
    )
    (comp (ref "TP1")
      (value "TEST-POINT-35")
      (footprint "eagle-import:TP_3535")
      (libsource (lib "eagle-import") (part "TEST-POINT-35"))
    )
    (comp (ref "TP2")
      (value "TEST-POINT-35")
      (footprint "eagle-import:TP_3535")
      (libsource (lib "eagle-import") (part "TEST-POINT-35"))
    )
    (comp (ref "TP3")
      (value "TEST-POINT-35")
      (footprint "eagle-import:TP_3535")
      (libsource (lib "eagle-import") (part "TEST-POINT-35"))
    )
    (comp (ref "TP4")
      (value "TEST-POINT-35")
      (footprint "eagle-import:TP_3535")
      (libsource (lib "eagle-import") (part "TEST-POINT-35"))
    )
    (comp (ref "TP5")
      (value "TEST-POINT-35")
      (footprint "eagle-import:TP_3535")
      (libsource (lib "eagle-import") (part "TEST-POINT-35"))
    )
    (comp (ref "TP7")
      (value "TEST-POINT-35")
      (footprint "eagle-import:TP_3535")
      (libsource (lib "eagle-import") (part "TEST-POINT-35"))
    )
    (comp (ref "TP8")
      (value "TEST-POINT-35")
      (footprint "eagle-import:TP_3535")
      (libsource (lib "eagle-import") (part "TEST-POINT-35"))
    )
    (comp (ref "TP9")
      (value "TEST-POINT-35")
      (footprint "eagle-import:TP_3535")
      (libsource (lib "eagle-import") (part "TEST-POINT-35"))
    )
    (comp (ref "TP10")
      (value "TEST-POINT-35")
      (footprint "eagle-import:TP_3535")
      (libsource (lib "eagle-import") (part "TEST-POINT-35"))
    )
    (comp (ref "TP11")
      (value "TEST-POINT-35")
      (footprint "eagle-import:TP_3535")
      (libsource (lib "eagle-import") (part "TEST-POINT-35"))
    )
    (comp (ref "TP12")
      (value "TEST-POINT-35")
      (footprint "eagle-import:TP_3535")
      (libsource (lib "eagle-import") (part "TEST-POINT-35"))
    )
    (comp (ref "TP13")
      (value "TEST-POINT-35")
      (footprint "eagle-import:TP_3535")
      (libsource (lib "eagle-import") (part "TEST-POINT-35"))
    )
    (comp (ref "TP14")
      (value "TEST-POINT-35")
      (footprint "eagle-import:TP_3535")
      (libsource (lib "eagle-import") (part "TEST-POINT-35"))
    )
    (comp (ref "TP15")
      (value "TEST-POINT'4545'")
      (footprint "eagle-import:TP-D45MIL")
      (fields (field (name "PARTNO") "DNP"))
      (libsource (lib "eagle-import") (part "TEST-POINT'4545'"))
    )
    (comp (ref "TP16")
      (value "TEST-POINT-1.9X0.3MM")
      (footprint "eagle-import:TEST-1.9X0.3MM")
      (libsource (lib "eagle-import") (part "TEST-POINT-1.9X0.3MM"))
    )
    (comp (ref "TP17")
      (value "TEST-POINT-1.9X0.3MM")
      (footprint "eagle-import:TEST-1.9X0.3MM")
      (libsource (lib "eagle-import") (part "TEST-POINT-1.9X0.3MM"))
    )
    (comp (ref "U1")
      (value "SX1302IMLTRT")
      (footprint "eagle-import:QFN68-0.35-7X7X0.75MM")
      (libsource (lib "eagle-import") (part "TRANSCEIVER-SX1302"))
    )
    (comp (ref "U2")
      (value "HDF915C1-S6")
      (footprint "eagle-import:FILTER6P-1.1-3X3X1.3MM")
      (libsource (lib "eagle-import") (part "FILTER-B39871B3717U410"))
    )
    (comp (ref "U5")
      (value "SX1250IMLTRT")
      (footprint "eagle-import:QFN24G-0.5-4X4MM")
      (libsource (lib "eagle-import") (part "RF-SX1250"))
    )
    (comp (ref "U6")
      (value "MP2161GJ")
      (footprint "eagle-import:TSOT23-8")
      (libsource (lib "eagle-import") (part "PMIC-MP2161'GJ'"))
    )
    (comp (ref "U7")
      (value "SX1250IMLTRT")
      (footprint "eagle-import:QFN24G-0.5-4X4MM")
      (libsource (lib "eagle-import") (part "RF-SX1250"))
    )
    (comp (ref "U8")
      (value "HDF915C1-S6")
      (footprint "eagle-import:FILTER6P-1.1-3X3X1.3MM")
      (libsource (lib "eagle-import") (part "FILTER-B39871B3717U410"))
    )
    (comp (ref "U9")
      (value "SKY66420-11")
      (footprint "eagle-import:MODULE16P-0.5-3X3X0.75MM")
      (libsource (lib "eagle-import") (part "MODULE-RF-SKY66420-11"))
    )
    (comp (ref "U10")
      (value "HDF915C1-S6")
      (footprint "eagle-import:FILTER6P-1.1-3X3X1.3MM")
      (libsource (lib "eagle-import") (part "FILTER-B39871B3717U410"))
    )
    (comp (ref "U11")
      (value "DNP")
      (footprint "eagle-import:QFN24G-0.5-4X4MM")
      (libsource (lib "eagle-import") (part "TRANSCEIVER-SX1261/2"))
    )
    (comp (ref "U13")
      (value "STTS751")
      (footprint "eagle-import:UDFN-6L")
      (libsource (lib "eagle-import") (part "SENSOR-STTS751"))
    )
    (comp (ref "U14")
      (value "N32G4FRKEQ7")
      (footprint "eagle-import:QFN32G-0.4-4X4MM")
      (libsource (lib "eagle-import") (part "MCU-N32G4FRKCQ7"))
    )
    (comp (ref "X1")
      (value "DSB221SDN")
      (footprint "eagle-import:X4-SMD-2.5X2.0X1.0MM")
      (libsource (lib "eagle-import") (part "CRYSTAL-OSCILLATOR-2520"))
    )
    (comp (ref "X3")
      (value "DNP")
      (footprint "eagle-import:X2-SMD-3.2X1.5X0.55MM")
      (libsource (lib "eagle-import") (part "CRYSTAL-2P-3215"))
    )
  )
  (nets
    (net (code "1") (name "32MHZ") (class "Default")
      (node (ref "R37") (pin "2") (pinfunction "2_2") (pintype "passive"))
      (node (ref "R6") (pin "2") (pinfunction "2_2") (pintype "passive"))
      (node (ref "R9") (pin "2") (pinfunction "2_2") (pintype "passive"))
      (node (ref "X1") (pin "3") (pinfunction "OUT_3") (pintype "bidirectional"))
    )
    (net (code "2") (name "1302_CS") (class "Default")
      (node (ref "R33") (pin "2") (pinfunction "2_2") (pintype "passive"))
      (node (ref "R43") (pin "1") (pinfunction "1_1") (pintype "passive"))
      (node (ref "U1") (pin "1") (pinfunction "HOST_CSN_1") (pintype "bidirectional"))
      (node (ref "U14") (pin "13") (pinfunction "PC4_13") (pintype "bidirectional"))
    )
    (net (code "3") (name "1302_RESET") (class "Default")
      (node (ref "C1") (pin "2") (pinfunction "2_2") (pintype "passive"))
      (node (ref "D7") (pin "-") (pinfunction "-_-") (pintype "passive"))
      (node (ref "R1") (pin "2") (pinfunction "2_2") (pintype "passive"))
      (node (ref "U1") (pin "7") (pinfunction "RESET_7") (pintype "bidirectional"))
      (node (ref "U14") (pin "14") (pinfunction "PC5_14") (pintype "bidirectional"))
    )
    (net (code "4") (name "1302_RESET_HOST") (class "Default")
      (node (ref "D7") (pin "+") (pinfunction "+_+") (pintype "passive"))
      (node (ref "R59") (pin "1") (pinfunction "1_1") (pintype "passive"))
    )
    (net (code "5") (name "CONFIG_OK") (class "Default")
      (node (ref "R31") (pin "1") (pinfunction "1_1") (pintype "passive"))
      (node (ref "U1") (pin "66") (pinfunction "GPIO0_66") (pintype "bidirectional"))
    )
    (net (code "6") (name "CS_PCIE") (class "Default")
      (node (ref "J1") (pin "51") (pinfunction "51_51") (pintype "bidirectional"))
      (node (ref "R43") (pin "2") (pinfunction "2_2") (pintype "passive"))
    )
    (net (code "7") (name "DM") (class "Default")
      (node (ref "J1") (pin "36") (pinfunction "36_36") (pintype "bidirectional"))
      (node (ref "R66") (pin "1") (pinfunction "1_1") (pintype "passive"))
    )
    (net (code "8") (name "DP") (class "Default")
      (node (ref "J1") (pin "38") (pinfunction "38_38") (pintype "bidirectional"))
      (node (ref "R64") (pin "1") (pinfunction "1_1") (pintype "passive"))
    )
    (net (code "9") (name "FEM_CS") (class "Default")
      (node (ref "R14") (pin "2") (pinfunction "2_2") (pintype "passive"))
      (node (ref "R34") (pin "1") (pinfunction "1_1") (pintype "passive"))
      (node (ref "U1") (pin "10") (pinfunction "RADIO_CTRL0_10") (pintype "bidirectional"))
    )
    (net (code "10") (name "FEM_PA_ON") (class "Default")
      (node (ref "R15") (pin "2") (pinfunction "2_2") (pintype "passive"))
      (node (ref "U1") (pin "16") (pinfunction "RADIO_CTRL4_16") (pintype "bidirectional"))
    )
    (net (code "11") (name "GND_POWER") (class "Default")
      (node (ref "ANT1") (pin "GND1") (pinfunction "GND1_GND1") (pintype "bidirectional"))
      (node (ref "ANT1") (pin "GND2") (pinfunction "GND2_GND2") (pintype "bidirectional"))
      (node (ref "ANT2") (pin "GND1") (pinfunction "GND1_GND1") (pintype "bidirectional"))
      (node (ref "ANT2") (pin "GND2") (pinfunction "GND2_GND2") (pintype "bidirectional"))
      (node (ref "C12") (pin "1") (pinfunction "1_1") (pintype "passive"))
      (node (ref "C13") (pin "1") (pinfunction "1_1") (pintype "passive"))
      (node (ref "C16") (pin "1") (pinfunction "1_1") (pintype "passive"))
      (node (ref "C17") (pin "1") (pinfunction "1_1") (pintype "passive"))
      (node (ref "C18") (pin "1") (pinfunction "1_1") (pintype "passive"))
      (node (ref "C19") (pin "1") (pinfunction "1_1") (pintype "passive"))
      (node (ref "C2") (pin "1") (pinfunction "1_1") (pintype "passive"))
      (node (ref "C20") (pin "1") (pinfunction "1_1") (pintype "passive"))
      (node (ref "C21") (pin "1") (pinfunction "1_1") (pintype "passive"))
      (node (ref "C22") (pin "1") (pinfunction "1_1") (pintype "passive"))
      (node (ref "C23") (pin "1") (pinfunction "1_1") (pintype "passive"))
      (node (ref "C24") (pin "1") (pinfunction "1_1") (pintype "passive"))
      (node (ref "C25") (pin "1") (pinfunction "1_1") (pintype "passive"))
      (node (ref "C28") (pin "1") (pinfunction "1_1") (pintype "passive"))
      (node (ref "C29") (pin "1") (pinfunction "1_1") (pintype "passive"))
      (node (ref "C3") (pin "1") (pinfunction "1_1") (pintype "passive"))
      (node (ref "C30") (pin "1") (pinfunction "1_1") (pintype "passive"))
      (node (ref "C31") (pin "1") (pinfunction "1_1") (pintype "passive"))
      (node (ref "C34") (pin "1") (pinfunction "1_1") (pintype "passive"))
      (node (ref "C35") (pin "1") (pinfunction "1_1") (pintype "passive"))
      (node (ref "C36") (pin "1") (pinfunction "1_1") (pintype "passive"))
      (node (ref "C37") (pin "1") (pinfunction "1_1") (pintype "passive"))
      (node (ref "C39") (pin "1") (pinfunction "1_1") (pintype "passive"))
      (node (ref "C40") (pin "1") (pinfunction "1_1") (pintype "passive"))
      (node (ref "C41") (pin "1") (pinfunction "1_1") (pintype "passive"))
      (node (ref "C42") (pin "1") (pinfunction "1_1") (pintype "passive"))
      (node (ref "C43") (pin "1") (pinfunction "1_1") (pintype "passive"))
      (node (ref "C44") (pin "1") (pinfunction "1_1") (pintype "passive"))
      (node (ref "C45") (pin "1") (pinfunction "1_1") (pintype "passive"))
      (node (ref "C46") (pin "1") (pinfunction "1_1") (pintype "passive"))
      (node (ref "C47") (pin "1") (pinfunction "1_1") (pintype "passive"))
      (node (ref "C48") (pin "1") (pinfunction "1_1") (pintype "passive"))
      (node (ref "C49") (pin "1") (pinfunction "1_1") (pintype "passive"))
      (node (ref "C5") (pin "1") (pinfunction "1_1") (pintype "passive"))
      (node (ref "C50") (pin "1") (pinfunction "1_1") (pintype "passive"))
      (node (ref "C51") (pin "1") (pinfunction "1_1") (pintype "passive"))
      (node (ref "C52") (pin "1") (pinfunction "1_1") (pintype "passive"))
      (node (ref "C55") (pin "1") (pinfunction "1_1") (pintype "passive"))
      (node (ref "C56") (pin "1") (pinfunction "1_1") (pintype "passive"))
      (node (ref "C57") (pin "1") (pinfunction "1_1") (pintype "passive"))
      (node (ref "C58") (pin "1") (pinfunction "1_1") (pintype "passive"))
      (node (ref "C60") (pin "2") (pinfunction "2_2") (pintype "passive"))
      (node (ref "C61") (pin "2") (pinfunction "2_2") (pintype "passive"))
      (node (ref "C62") (pin "1") (pinfunction "1_1") (pintype "passive"))
      (node (ref "C63") (pin "2") (pinfunction "2_2") (pintype "passive"))
      (node (ref "C65") (pin "2") (pinfunction "2_2") (pintype "passive"))
      (node (ref "C67") (pin "2") (pinfunction "2_2") (pintype "passive"))
      (node (ref "C69") (pin "1") (pinfunction "1_1") (pintype "passive"))
      (node (ref "C7") (pin "1") (pinfunction "1_1") (pintype "passive"))
      (node (ref "C70") (pin "1") (pinfunction "1_1") (pintype "passive"))
      (node (ref "C71") (pin "1") (pinfunction "1_1") (pintype "passive"))
      (node (ref "C72") (pin "1") (pinfunction "1_1") (pintype "passive"))
      (node (ref "C73") (pin "2") (pinfunction "2_2") (pintype "passive"))
      (node (ref "C74") (pin "2") (pinfunction "2_2") (pintype "passive"))
      (node (ref "C76") (pin "1") (pinfunction "1_1") (pintype "passive"))
      (node (ref "C77") (pin "2") (pinfunction "2_2") (pintype "passive"))
      (node (ref "C78") (pin "2") (pinfunction "2_2") (pintype "passive"))
      (node (ref "C80") (pin "1") (pinfunction "1_1") (pintype "passive"))
      (node (ref "C81") (pin "2") (pinfunction "2_2") (pintype "passive"))
      (node (ref "C82") (pin "2") (pinfunction "2_2") (pintype "passive"))
      (node (ref "C83") (pin "1") (pinfunction "1_1") (pintype "passive"))
      (node (ref "C84") (pin "2") (pinfunction "2_2") (pintype "passive"))
      (node (ref "C85") (pin "1") (pinfunction "1_1") (pintype "passive"))
      (node (ref "C86") (pin "1") (pinfunction "1_1") (pintype "passive"))
      (node (ref "C87") (pin "1") (pinfunction "1_1") (pintype "passive"))
      (node (ref "C88") (pin "1") (pinfunction "1_1") (pintype "passive"))
      (node (ref "C89") (pin "1") (pinfunction "1_1") (pintype "passive"))
      (node (ref "C9") (pin "1") (pinfunction "1_1") (pintype "passive"))
      (node (ref "C90") (pin "1") (pinfunction "1_1") (pintype "passive"))
      (node (ref "C92") (pin "1") (pinfunction "1_1") (pintype "passive"))
      (node (ref "D1") (pin "-") (pinfunction "-_-") (pintype "passive"))
      (node (ref "D2") (pin "-") (pinfunction "-_-") (pintype "passive"))
      (node (ref "D3") (pin "-") (pinfunction "-_-") (pintype "passive"))
      (node (ref "D4") (pin "-") (pinfunction "-_-") (pintype "passive"))
      (node (ref "D5") (pin "1") (pinfunction "1_1") (pintype "bidirectional"))
      (node (ref "D6") (pin "1") (pinfunction "1_1") (pintype "bidirectional"))
      (node (ref "J1") (pin "15") (pinfunction "GND_15") (pintype "bidirectional"))
      (node (ref "J1") (pin "18") (pinfunction "GND_18") (pintype "bidirectional"))
      (node (ref "J1") (pin "21") (pinfunction "GND_21") (pintype "bidirectional"))
      (node (ref "J1") (pin "26") (pinfunction "GND_26") (pintype "bidirectional"))
      (node (ref "J1") (pin "27") (pinfunction "GND_27") (pintype "bidirectional"))
      (node (ref "J1") (pin "29") (pinfunction "GND_29") (pintype "bidirectional"))
      (node (ref "J1") (pin "34") (pinfunction "GND_34") (pintype "bidirectional"))
      (node (ref "J1") (pin "35") (pinfunction "GND_35") (pintype "bidirectional"))
      (node (ref "J1") (pin "37") (pinfunction "GND_37") (pintype "bidirectional"))
      (node (ref "J1") (pin "4") (pinfunction "GND_4") (pintype "bidirectional"))
      (node (ref "J1") (pin "40") (pinfunction "GND_40") (pintype "bidirectional"))
      (node (ref "J1") (pin "43") (pinfunction "GND_43") (pintype "bidirectional"))
      (node (ref "J1") (pin "50") (pinfunction "GND_50") (pintype "bidirectional"))
      (node (ref "J1") (pin "9") (pinfunction "GND_9") (pintype "bidirectional"))
      (node (ref "J1") (pin "S1") (pinfunction "GND_S1") (pintype "bidirectional"))
      (node (ref "J1") (pin "S2") (pinfunction "GND_S2") (pintype "bidirectional"))
      (node (ref "Q10") (pin "2") (pinfunction "S_2") (pintype "passive"))
      (node (ref "R1") (pin "1") (pinfunction "1_1") (pintype "passive"))
      (node (ref "R11") (pin "1") (pinfunction "1_1") (pintype "passive"))
      (node (ref "R12") (pin "1") (pinfunction "1_1") (pintype "passive"))
      (node (ref "R4") (pin "1") (pinfunction "1_1") (pintype "passive"))
      (node (ref "R53") (pin "1") (pinfunction "1_1") (pintype "passive"))
      (node (ref "R53") (pin "2") (pinfunction "2_2") (pintype "passive"))
      (node (ref "R54") (pin "1") (pinfunction "1_1") (pintype "passive"))
      (node (ref "R54") (pin "2") (pinfunction "2_2") (pintype "passive"))
      (node (ref "R55") (pin "1") (pinfunction "1_1") (pintype "passive"))
      (node (ref "R55") (pin "2") (pinfunction "2_2") (pintype "passive"))
      (node (ref "R57") (pin "2") (pinfunction "2_2") (pintype "passive"))
      (node (ref "R73") (pin "1") (pinfunction "1_1") (pintype "passive"))
      (node (ref "R74") (pin "1") (pinfunction "1_1") (pintype "passive"))
      (node (ref "R74") (pin "2") (pinfunction "2_2") (pintype "passive"))
      (node (ref "R87") (pin "1") (pinfunction "1_1") (pintype "passive"))
      (node (ref "S1") (pin "1") (pinfunction "S1_1") (pintype "bidirectional"))
      (node (ref "TP16") (pin "1") (pinfunction "T_1") (pintype "bidirectional"))
      (node (ref "TP17") (pin "1") (pinfunction "T_1") (pintype "bidirectional"))
      (node (ref "TP3") (pin "T") (pinfunction "T_T") (pintype "bidirectional"))
      (node (ref "U1") (pin "15") (pinfunction "GND_15") (pintype "bidirectional"))
      (node (ref "U1") (pin "20") (pinfunction "SP_VALID_20") (pintype "bidirectional"))
      (node (ref "U1") (pin "24") (pinfunction "GND_24") (pintype "bidirectional"))
      (node (ref "U1") (pin "25") (pinfunction "GND_25") (pintype "bidirectional"))
      (node (ref "U1") (pin "39") (pinfunction "GND_39") (pintype "bidirectional"))
      (node (ref "U1") (pin "46") (pinfunction "GND_46") (pintype "bidirectional"))
      (node (ref "U1") (pin "55") (pinfunction "GND_55") (pintype "bidirectional"))
      (node (ref "U1") (pin "6") (pinfunction "GND_6") (pintype "bidirectional"))
      (node (ref "U1") (pin "62") (pinfunction "GND_62") (pintype "bidirectional"))
      (node (ref "U1") (pin "69") (pinfunction "GND_69") (pintype "bidirectional"))
      (node (ref "U1") (pin "9") (pinfunction "GND_9") (pintype "bidirectional"))
      (node (ref "U10") (pin "1") (pinfunction "GND_1") (pintype "bidirectional"))
      (node (ref "U10") (pin "3") (pinfunction "GND_3") (pintype "bidirectional"))
      (node (ref "U10") (pin "4") (pinfunction "GND_4") (pintype "bidirectional"))
      (node (ref "U10") (pin "6") (pinfunction "GND_6") (pintype "bidirectional"))
      (node (ref "U11") (pin "2") (pinfunction "GND_2") (pintype "bidirectional"))
      (node (ref "U11") (pin "20") (pinfunction "GND_20") (pintype "bidirectional"))
      (node (ref "U11") (pin "5") (pinfunction "GND_5") (pintype "bidirectional"))
      (node (ref "U11") (pin "8") (pinfunction "GND_8") (pintype "bidirectional"))
      (node (ref "U11") (pin "PAD") (pinfunction "PAD_PAD") (pintype "bidirectional"))
      (node (ref "U13") (pin "4") (pinfunction "ADDR/~{THERM}_4") (pintype "bidirectional"))
      (node (ref "U13") (pin "5") (pinfunction "GND_5") (pintype "bidirectional"))
      (node (ref "U14") (pin "23") (pinfunction "VSS_2_23") (pintype "bidirectional"))
      (node (ref "U14") (pin "31") (pinfunction "VSS_3_31") (pintype "bidirectional"))
      (node (ref "U14") (pin "33") (pinfunction "PAD_33") (pintype "bidirectional"))
      (node (ref "U14") (pin "6") (pinfunction "VSSA_6") (pintype "bidirectional"))
      (node (ref "U2") (pin "1") (pinfunction "GND_1") (pintype "bidirectional"))
      (node (ref "U2") (pin "3") (pinfunction "GND_3") (pintype "bidirectional"))
      (node (ref "U2") (pin "4") (pinfunction "GND_4") (pintype "bidirectional"))
      (node (ref "U2") (pin "6") (pinfunction "GND_6") (pintype "bidirectional"))
      (node (ref "U5") (pin "20") (pinfunction "GND_20") (pintype "bidirectional"))
      (node (ref "U5") (pin "7") (pinfunction "GND_7") (pintype "bidirectional"))
      (node (ref "U5") (pin "PAD") (pinfunction "PAD_PAD") (pintype "bidirectional"))
      (node (ref "U6") (pin "4") (pinfunction "PGND_4") (pintype "bidirectional"))
      (node (ref "U6") (pin "6") (pinfunction "AGND_6") (pintype "bidirectional"))
      (node (ref "U7") (pin "20") (pinfunction "GND_20") (pintype "bidirectional"))
      (node (ref "U7") (pin "7") (pinfunction "GND_7") (pintype "bidirectional"))
      (node (ref "U7") (pin "PAD") (pinfunction "PAD_PAD") (pintype "bidirectional"))
      (node (ref "U8") (pin "1") (pinfunction "GND_1") (pintype "bidirectional"))
      (node (ref "U8") (pin "3") (pinfunction "GND_3") (pintype "bidirectional"))
      (node (ref "U8") (pin "4") (pinfunction "GND_4") (pintype "bidirectional"))
      (node (ref "U8") (pin "6") (pinfunction "GND_6") (pintype "bidirectional"))
      (node (ref "U9") (pin "10") (pinfunction "GND_10") (pintype "bidirectional"))
      (node (ref "U9") (pin "12") (pinfunction "GND_12") (pintype "bidirectional"))
      (node (ref "U9") (pin "17") (pinfunction "EPAD_17") (pintype "bidirectional"))
      (node (ref "X1") (pin "2") (pinfunction "GND_2") (pintype "bidirectional"))
    )
    (net (code "12") (name "I2C_SCL") (class "Default")
      (node (ref "R68") (pin "2") (pinfunction "2_2") (pintype "passive"))
      (node (ref "R81") (pin "1") (pinfunction "1_1") (pintype "passive"))
      (node (ref "U13") (pin "1") (pinfunction "SCL_1") (pintype "bidirectional"))
      (node (ref "U14") (pin "15") (pinfunction "PB10_15") (pintype "bidirectional"))
    )
    (net (code "13") (name "I2C_SDA") (class "Default")
      (node (ref "R58") (pin "2") (pinfunction "2_2") (pintype "passive"))
      (node (ref "R75") (pin "1") (pinfunction "1_1") (pintype "passive"))
      (node (ref "U13") (pin "6") (pinfunction "SDA_6") (pintype "bidirectional"))
      (node (ref "U14") (pin "16") (pinfunction "PB11_16") (pintype "bidirectional"))
    )
    (net (code "14") (name "MCU_RESET") (class "Default")
      (node (ref "C85") (pin "2") (pinfunction "2_2") (pintype "passive"))
      (node (ref "R71") (pin "2") (pinfunction "2_2") (pintype "passive"))
      (node (ref "R77") (pin "1") (pinfunction "1_1") (pintype "passive"))
      (node (ref "TP5") (pin "T") (pinfunction "T_T") (pintype "bidirectional"))
      (node (ref "U14") (pin "5") (pinfunction "NRST_5") (pintype "bidirectional"))
    )
    (net (code "15") (name "MISO") (class "Default")
      (node (ref "R44") (pin "1") (pinfunction "1_1") (pintype "passive"))
      (node (ref "R45") (pin "1") (pinfunction "1_1") (pintype "passive"))
      (node (ref "U1") (pin "2") (pinfunction "HOST_MISO_2") (pintype "bidirectional"))
      (node (ref "U11") (pin "16") (pinfunction "MISO_16") (pintype "bidirectional"))
    )
    (net (code "16") (name "MISO_A") (class "Default")
      (node (ref "U1") (pin "42") (pinfunction "RADIO_A_MISO_42") (pintype "bidirectional"))
      (node (ref "U5") (pin "16") (pinfunction "MISO_16") (pintype "bidirectional"))
    )
    (net (code "17") (name "MISO_B") (class "Default")
      (node (ref "U1") (pin "33") (pinfunction "RADIO_B_MISO_33") (pintype "bidirectional"))
      (node (ref "U7") (pin "16") (pinfunction "MISO_16") (pintype "bidirectional"))
    )
    (net (code "18") (name "MISO_PCIE") (class "Default")
      (node (ref "R39") (pin "1") (pinfunction "1_1") (pintype "passive"))
      (node (ref "R44") (pin "2") (pinfunction "2_2") (pintype "passive"))
    )
    (net (code "19") (name "MOSI") (class "Default")
      (node (ref "R40") (pin "2") (pinfunction "2_2") (pintype "passive"))
      (node (ref "R46") (pin "1") (pinfunction "1_1") (pintype "passive"))
      (node (ref "R48") (pin "1") (pinfunction "1_1") (pintype "passive"))
      (node (ref "R5") (pin "2") (pinfunction "2_2") (pintype "passive"))
    )
    (net (code "20") (name "MOSI_A") (class "Default")
      (node (ref "U1") (pin "67") (pinfunction "RADIO_A_MOSI_67") (pintype "bidirectional"))
      (node (ref "U5") (pin "17") (pinfunction "MOSI_17") (pintype "bidirectional"))
    )
    (net (code "21") (name "MOSI_B") (class "Default")
      (node (ref "U1") (pin "19") (pinfunction "RADIO_B_MOSI_19") (pintype "bidirectional"))
      (node (ref "U7") (pin "17") (pinfunction "MOSI_17") (pintype "bidirectional"))
    )
    (net (code "22") (name "MOSI_PCIE") (class "Default")
      (node (ref "J1") (pin "49") (pinfunction "49_49") (pintype "bidirectional"))
      (node (ref "R46") (pin "2") (pinfunction "2_2") (pintype "passive"))
    )
    (net (code "23") (name "Net-(ANT1-PadD)") (class "Default")
      (node (ref "ANT1") (pin "D") (pinfunction "D_D") (pintype "bidirectional"))
      (node (ref "C64") (pin "2") (pinfunction "2_2") (pintype "passive"))
      (node (ref "D5") (pin "2") (pinfunction "2_2") (pintype "bidirectional"))
    )
    (net (code "24") (name "Net-(ANT2-PadD)") (class "Default")
      (node (ref "ANT2") (pin "D") (pinfunction "D_D") (pintype "bidirectional"))
      (node (ref "C79") (pin "2") (pinfunction "2_2") (pintype "passive"))
      (node (ref "D6") (pin "2") (pinfunction "2_2") (pintype "bidirectional"))
    )
    (net (code "25") (name "Net-(C1-Pad1)") (class "Default")
      (node (ref "C1") (pin "1") (pinfunction "1_1") (pintype "passive"))
      (node (ref "R80") (pin "1") (pinfunction "1_1") (pintype "passive"))
    )
    (net (code "26") (name "Net-(C4-Pad1)") (class "Default")
      (node (ref "C4") (pin "1") (pinfunction "1_1") (pintype "passive"))
      (node (ref "C8") (pin "2") (pinfunction "2_2") (pintype "passive"))
      (node (ref "R12") (pin "2") (pinfunction "2_2") (pintype "passive"))
    )
    (net (code "27") (name "Net-(C14-Pad2)") (class "Default")
      (node (ref "C14") (pin "2") (pinfunction "2_2") (pintype "passive"))
      (node (ref "R6") (pin "1") (pinfunction "1_1") (pintype "passive"))
    )
    (net (code "28") (name "Net-(C38-Pad2)") (class "Default")
      (node (ref "C38") (pin "2") (pinfunction "2_2") (pintype "passive"))
      (node (ref "R9") (pin "1") (pinfunction "1_1") (pintype "passive"))
    )
    (net (code "29") (name "Net-(C53-Pad2)") (class "Default")
      (node (ref "C53") (pin "2") (pinfunction "2_2") (pintype "passive"))
      (node (ref "C54") (pin "1") (pinfunction "1_1") (pintype "passive"))
      (node (ref "C7") (pin "2") (pinfunction "2_2") (pintype "passive"))
      (node (ref "L10") (pin "2") (pinfunction "2_2") (pintype "passive"))
    )
    (net (code "30") (name "Net-(C54-Pad2)") (class "Default")
      (node (ref "C54") (pin "2") (pinfunction "2_2") (pintype "passive"))
      (node (ref "L11") (pin "1") (pinfunction "1_1") (pintype "passive"))
    )
    (net (code "31") (name "Net-(C56-Pad2)") (class "Default")
      (node (ref "C56") (pin "2") (pinfunction "2_2") (pintype "passive"))
      (node (ref "C57") (pin "2") (pinfunction "2_2") (pintype "passive"))
      (node (ref "L16") (pin "1") (pinfunction "1_1") (pintype "passive"))
      (node (ref "L8") (pin "2") (pinfunction "2_2") (pintype "passive"))
    )
    (net (code "32") (name "Net-(C59-Pad1)") (class "Default")
      (node (ref "C59") (pin "1") (pinfunction "1_1") (pintype "passive"))
      (node (ref "C91") (pin "2") (pinfunction "2_2") (pintype "passive"))
    )
    (net (code "33") (name "Net-(C61-Pad1)") (class "Default")
      (node (ref "C61") (pin "1") (pinfunction "1_1") (pintype "passive"))
      (node (ref "C91") (pin "1") (pinfunction "1_1") (pintype "passive"))
      (node (ref "L17") (pin "2") (pinfunction "2_2") (pintype "passive"))
      (node (ref "L24") (pin "1") (pinfunction "1_1") (pintype "passive"))
    )
    (net (code "34") (name "Net-(C64-Pad1)") (class "Default")
      (node (ref "C64") (pin "1") (pinfunction "1_1") (pintype "passive"))
      (node (ref "C82") (pin "1") (pinfunction "1_1") (pintype "passive"))
      (node (ref "L24") (pin "2") (pinfunction "2_2") (pintype "passive"))
    )
    (net (code "35") (name "Net-(C66-Pad2)") (class "Default")
      (node (ref "C66") (pin "2") (pinfunction "2_2") (pintype "passive"))
      (node (ref "R37") (pin "1") (pinfunction "1_1") (pintype "passive"))
    )
    (net (code "36") (name "Net-(C68-Pad1)") (class "Default")
      (node (ref "C68") (pin "1") (pinfunction "1_1") (pintype "passive"))
      (node (ref "C74") (pin "1") (pinfunction "1_1") (pintype "passive"))
      (node (ref "C75") (pin "2") (pinfunction "2_2") (pintype "passive"))
    )
    (net (code "37") (name "Net-(C77-Pad1)") (class "Default")
      (node (ref "C77") (pin "1") (pinfunction "1_1") (pintype "passive"))
      (node (ref "L21") (pin "1") (pinfunction "1_1") (pintype "passive"))
      (node (ref "R62") (pin "2") (pinfunction "2_2") (pintype "passive"))
    )
    (net (code "38") (name "Net-(C78-Pad1)") (class "Default")
      (node (ref "C78") (pin "1") (pinfunction "1_1") (pintype "passive"))
      (node (ref "C79") (pin "1") (pinfunction "1_1") (pintype "passive"))
      (node (ref "L21") (pin "2") (pinfunction "2_2") (pintype "passive"))
    )
    (net (code "39") (name "Net-(D1-Pad+)") (class "Default")
      (node (ref "D1") (pin "+") (pinfunction "+_+") (pintype "passive"))
      (node (ref "R30") (pin "2") (pinfunction "2_2") (pintype "passive"))
    )
    (net (code "40") (name "Net-(D2-Pad+)") (class "Default")
      (node (ref "D2") (pin "+") (pinfunction "+_+") (pintype "passive"))
      (node (ref "R31") (pin "2") (pinfunction "2_2") (pintype "passive"))
    )
    (net (code "41") (name "Net-(D3-Pad+)") (class "Default")
      (node (ref "D3") (pin "+") (pinfunction "+_+") (pintype "passive"))
      (node (ref "R32") (pin "2") (pinfunction "2_2") (pintype "passive"))
    )
    (net (code "42") (name "Net-(D4-Pad+)") (class "Default")
      (node (ref "D4") (pin "+") (pinfunction "+_+") (pintype "passive"))
      (node (ref "R47") (pin "2") (pinfunction "2_2") (pintype "passive"))
    )
    (net (code "43") (name "Net-(J1-Pad30)") (class "Default")
      (node (ref "J1") (pin "30") (pinfunction "30_30") (pintype "bidirectional"))
      (node (ref "R81") (pin "2") (pinfunction "2_2") (pintype "passive"))
    )
    (net (code "44") (name "Net-(J1-Pad32)") (class "Default")
      (node (ref "J1") (pin "32") (pinfunction "32_32") (pintype "bidirectional"))
      (node (ref "R75") (pin "2") (pinfunction "2_2") (pintype "passive"))
    )
    (net (code "45") (name "Net-(J1-Pad47)") (class "Default")
      (node (ref "J1") (pin "47") (pinfunction "47_47") (pintype "bidirectional"))
      (node (ref "R39") (pin "2") (pinfunction "2_2") (pintype "passive"))
    )
    (net (code "46") (name "Net-(Q10-D)") (class "Default")
      (node (ref "Q10") (pin "3") (pinfunction "D_3") (pintype "passive"))
      (node (ref "Q8") (pin "1") (pinfunction "G_1") (pintype "passive"))
      (node (ref "R78") (pin "2") (pinfunction "2_2") (pintype "passive"))
    )
    (net (code "47") (name "Net-(Q10-G)") (class "Default")
      (node (ref "C92") (pin "2") (pinfunction "2_2") (pintype "passive"))
      (node (ref "Q10") (pin "1") (pinfunction "G_1") (pintype "passive"))
      (node (ref "R79") (pin "2") (pinfunction "2_2") (pintype "passive"))
    )
    (net (code "48") (name "Net-(U1-HOST_MOSI)") (class "Default")
      (node (ref "R5") (pin "1") (pinfunction "1_1") (pintype "passive"))
      (node (ref "U1") (pin "3") (pinfunction "HOST_MOSI_3") (pintype "bidirectional"))
    )
    (net (code "49") (name "Net-(U1-HOST_SCK)") (class "Default")
      (node (ref "R10") (pin "1") (pinfunction "1_1") (pintype "passive"))
      (node (ref "U1") (pin "4") (pinfunction "HOST_SCK_4") (pintype "bidirectional"))
    )
    (net (code "50") (name "Net-(U1-RADIO_A_CLK_I)") (class "Default")
      (node (ref "R25") (pin "1") (pinfunction "1_1") (pintype "passive"))
      (node (ref "U1") (pin "43") (pinfunction "RADIO_A_CLK_I_43") (pintype "bidirectional"))
    )
    (net (code "51") (name "Net-(U1-RADIO_A_IQ0)") (class "Default")
      (node (ref "R26") (pin "1") (pinfunction "1_1") (pintype "passive"))
      (node (ref "U1") (pin "44") (pinfunction "RADIO_A_IQ0_44") (pintype "bidirectional"))
    )
    (net (code "52") (name "Net-(U1-RADIO_A_IQ1)") (class "Default")
      (node (ref "R27") (pin "1") (pinfunction "1_1") (pintype "passive"))
      (node (ref "U1") (pin "45") (pinfunction "RADIO_A_IQ1_45") (pintype "bidirectional"))
    )
    (net (code "53") (name "Net-(U1-RADIO_A_IQ2)") (class "Default")
      (node (ref "R29") (pin "1") (pinfunction "1_1") (pintype "passive"))
      (node (ref "U1") (pin "49") (pinfunction "RADIO_A_IQ2_49") (pintype "bidirectional"))
    )
    (net (code "54") (name "Net-(U1-RADIO_A_IQ3)") (class "Default")
      (node (ref "R24") (pin "1") (pinfunction "1_1") (pintype "passive"))
      (node (ref "U1") (pin "41") (pinfunction "RADIO_A_IQ3_41") (pintype "bidirectional"))
    )
    (net (code "55") (name "Net-(U1-RADIO_A_IQ4)") (class "Default")
      (node (ref "R28") (pin "1") (pinfunction "1_1") (pintype "passive"))
      (node (ref "U1") (pin "48") (pinfunction "RADIO_A_IQ4_48") (pintype "bidirectional"))
    )
    (net (code "56") (name "Net-(U1-RADIO_B_CLK_I)") (class "Default")
      (node (ref "R19") (pin "1") (pinfunction "1_1") (pintype "passive"))
      (node (ref "U1") (pin "34") (pinfunction "RADIO_B_CLK_I_34") (pintype "bidirectional"))
    )
    (net (code "57") (name "Net-(U1-RADIO_B_IQ0)") (class "Default")
      (node (ref "R20") (pin "1") (pinfunction "1_1") (pintype "passive"))
      (node (ref "U1") (pin "35") (pinfunction "RADIO_B_IQ0_35") (pintype "bidirectional"))
    )
    (net (code "58") (name "Net-(U1-RADIO_B_IQ1)") (class "Default")
      (node (ref "R21") (pin "1") (pinfunction "1_1") (pintype "passive"))
      (node (ref "U1") (pin "36") (pinfunction "RADIO_B_IQ1_36") (pintype "bidirectional"))
    )
    (net (code "59") (name "Net-(U1-RADIO_B_IQ2)") (class "Default")
      (node (ref "R23") (pin "1") (pinfunction "1_1") (pintype "passive"))
      (node (ref "U1") (pin "38") (pinfunction "RADIO_B_IQ2_38") (pintype "bidirectional"))
    )
    (net (code "60") (name "Net-(U1-RADIO_B_IQ3)") (class "Default")
      (node (ref "R18") (pin "1") (pinfunction "1_1") (pintype "passive"))
      (node (ref "U1") (pin "32") (pinfunction "RADIO_B_IQ3_32") (pintype "bidirectional"))
    )
    (net (code "61") (name "Net-(U1-RADIO_B_IQ4)") (class "Default")
      (node (ref "R22") (pin "1") (pinfunction "1_1") (pintype "passive"))
      (node (ref "U1") (pin "37") (pinfunction "RADIO_B_IQ4_37") (pintype "bidirectional"))
    )
    (net (code "62") (name "Net-(U2-IN)") (class "Default")
      (node (ref "C11") (pin "1") (pinfunction "1_1") (pintype "passive"))
      (node (ref "U2") (pin "2") (pinfunction "IN_2") (pintype "bidirectional"))
    )
    (net (code "63") (name "Net-(U2-OUT)") (class "Default")
      (node (ref "C10") (pin "1") (pinfunction "1_1") (pintype "passive"))
      (node (ref "C6") (pin "1") (pinfunction "1_1") (pintype "passive"))
      (node (ref "C75") (pin "1") (pinfunction "1_1") (pintype "passive"))
      (node (ref "U2") (pin "5") (pinfunction "OUT_5") (pintype "bidirectional"))
    )
    (net (code "64") (name "Net-(U5-DCC_SW)") (class "Default")
      (node (ref "L6") (pin "2") (pinfunction "2_2") (pintype "passive"))
      (node (ref "U5") (pin "8") (pinfunction "DCC_SW_8") (pintype "bidirectional"))
    )
    (net (code "65") (name "Net-(U5-VREG)") (class "Default")
      (node (ref "C34") (pin "2") (pinfunction "2_2") (pintype "passive"))
      (node (ref "L6") (pin "1") (pinfunction "1_1") (pintype "passive"))
      (node (ref "L7") (pin "2") (pinfunction "2_2") (pintype "passive"))
      (node (ref "U5") (pin "6") (pinfunction "VREG_6") (pintype "bidirectional"))
    )
    (net (code "66") (name "Net-(U5-VR_PA)") (class "Default")
      (node (ref "C36") (pin "2") (pinfunction "2_2") (pintype "passive"))
      (node (ref "C37") (pin "2") (pinfunction "2_2") (pintype "passive"))
      (node (ref "L9") (pin "2") (pinfunction "2_2") (pintype "passive"))
      (node (ref "U5") (pin "1") (pinfunction "VR_PA_1") (pintype "bidirectional"))
    )
    (net (code "67") (name "Net-(U5-XTA)") (class "Default")
      (node (ref "C14") (pin "1") (pinfunction "1_1") (pintype "passive"))
      (node (ref "U5") (pin "3") (pinfunction "XTA_3") (pintype "bidirectional"))
    )
    (net (code "68") (name "Net-(U6-EN)") (class "Default")
      (node (ref "R82") (pin "2") (pinfunction "2_2") (pintype "passive"))
      (node (ref "U6") (pin "8") (pinfunction "EN_8") (pintype "bidirectional"))
    )
    (net (code "69") (name "Net-(U6-FB)") (class "Default")
      (node (ref "R83") (pin "1") (pinfunction "1_1") (pintype "passive"))
      (node (ref "R87") (pin "2") (pinfunction "2_2") (pintype "passive"))
      (node (ref "U6") (pin "7") (pinfunction "FB_7") (pintype "bidirectional"))
    )
    (net (code "70") (name "Net-(U6-PG)") (class "Default")
      (node (ref "TP15") (pin "T") (pinfunction "T_T") (pintype "bidirectional"))
      (node (ref "U6") (pin "1") (pinfunction "PG_1") (pintype "bidirectional"))
    )
    (net (code "71") (name "Net-(U6-SW)") (class "Default")
      (node (ref "L5") (pin "1") (pinfunction "1_1") (pintype "passive"))
      (node (ref "U6") (pin "3") (pinfunction "SW_3") (pintype "bidirectional"))
    )
    (net (code "72") (name "Net-(U7-DCC_SW)") (class "Default")
      (node (ref "L14") (pin "2") (pinfunction "2_2") (pintype "passive"))
      (node (ref "U7") (pin "8") (pinfunction "DCC_SW_8") (pintype "bidirectional"))
    )
    (net (code "73") (name "Net-(U7-VREG)") (class "Default")
      (node (ref "C46") (pin "2") (pinfunction "2_2") (pintype "passive"))
      (node (ref "L14") (pin "1") (pinfunction "1_1") (pintype "passive"))
      (node (ref "L15") (pin "2") (pinfunction "2_2") (pintype "passive"))
      (node (ref "U7") (pin "6") (pinfunction "VREG_6") (pintype "bidirectional"))
    )
    (net (code "74") (name "Net-(U7-XTA)") (class "Default")
      (node (ref "C38") (pin "1") (pinfunction "1_1") (pintype "passive"))
      (node (ref "U7") (pin "3") (pinfunction "XTA_3") (pintype "bidirectional"))
    )
    (net (code "75") (name "Net-(U8-IN)") (class "Default")
      (node (ref "C2") (pin "2") (pinfunction "2_2") (pintype "passive"))
      (node (ref "L11") (pin "2") (pinfunction "2_2") (pintype "passive"))
      (node (ref "U8") (pin "2") (pinfunction "IN_2") (pintype "bidirectional"))
    )
    (net (code "76") (name "Net-(U8-OUT)") (class "Default")
      (node (ref "C8") (pin "1") (pinfunction "1_1") (pintype "passive"))
      (node (ref "R11") (pin "2") (pinfunction "2_2") (pintype "passive"))
      (node (ref "U8") (pin "5") (pinfunction "OUT_5") (pintype "bidirectional"))
    )
    (net (code "77") (name "Net-(U9-ANT)") (class "Default")
      (node (ref "C59") (pin "2") (pinfunction "2_2") (pintype "passive"))
      (node (ref "C60") (pin "1") (pinfunction "1_1") (pintype "passive"))
      (node (ref "L17") (pin "1") (pinfunction "1_1") (pintype "passive"))
      (node (ref "U9") (pin "9") (pinfunction "ANT_9") (pintype "bidirectional"))
    )
    (net (code "78") (name "Net-(U9-CPS)") (class "Default")
      (node (ref "C17") (pin "2") (pinfunction "2_2") (pintype "passive"))
      (node (ref "R15") (pin "1") (pinfunction "1_1") (pintype "passive"))
      (node (ref "U9") (pin "5") (pinfunction "CPS_5") (pintype "bidirectional"))
    )
    (net (code "79") (name "Net-(U9-CSD)") (class "Default")
      (node (ref "C16") (pin "2") (pinfunction "2_2") (pintype "passive"))
      (node (ref "R14") (pin "1") (pinfunction "1_1") (pintype "passive"))
      (node (ref "U9") (pin "4") (pinfunction "CSD_4") (pintype "bidirectional"))
    )
    (net (code "80") (name "Net-(U9-CTX)") (class "Default")
      (node (ref "C18") (pin "2") (pinfunction "2_2") (pintype "passive"))
      (node (ref "R16") (pin "1") (pinfunction "1_1") (pintype "passive"))
      (node (ref "U9") (pin "6") (pinfunction "CTX_6") (pintype "bidirectional"))
    )
    (net (code "81") (name "Net-(U9-PA_OUT)") (class "Default")
      (node (ref "L2") (pin "1") (pinfunction "1_1") (pintype "passive"))
      (node (ref "L8") (pin "1") (pinfunction "1_1") (pintype "passive"))
      (node (ref "U9") (pin "13") (pinfunction "PA_OUT_13") (pintype "bidirectional"))
    )
    (net (code "82") (name "Net-(U9-RX)") (class "Default")
      (node (ref "C11") (pin "2") (pinfunction "2_2") (pintype "passive"))
      (node (ref "U9") (pin "2") (pinfunction "RX_2") (pintype "bidirectional"))
    )
    (net (code "83") (name "Net-(U9-RX_FLT)") (class "Default")
      (node (ref "R69") (pin "1") (pinfunction "1_1") (pintype "passive"))
      (node (ref "U9") (pin "8") (pinfunction "RX_FLT_8") (pintype "bidirectional"))
    )
    (net (code "84") (name "Net-(U9-TX)") (class "Default")
      (node (ref "C4") (pin "2") (pinfunction "2_2") (pintype "passive"))
      (node (ref "U9") (pin "1") (pinfunction "TX_1") (pintype "bidirectional"))
    )
    (net (code "85") (name "Net-(U9-TX_IN)") (class "Default")
      (node (ref "C58") (pin "2") (pinfunction "2_2") (pintype "passive"))
      (node (ref "L16") (pin "2") (pinfunction "2_2") (pintype "passive"))
      (node (ref "U9") (pin "11") (pinfunction "TX_IN_11") (pintype "bidirectional"))
    )
    (net (code "86") (name "Net-(U9-VCC1)") (class "Default")
      (node (ref "L1") (pin "1") (pinfunction "1_1") (pintype "passive"))
      (node (ref "U9") (pin "16") (pinfunction "VCC1_16") (pintype "bidirectional"))
    )
    (net (code "87") (name "Net-(U10-IN)") (class "Default")
      (node (ref "R62") (pin "1") (pinfunction "1_1") (pintype "passive"))
      (node (ref "R69") (pin "2") (pinfunction "2_2") (pintype "passive"))
      (node (ref "U10") (pin "2") (pinfunction "IN_2") (pintype "bidirectional"))
    )
    (net (code "88") (name "Net-(U10-OUT)") (class "Default")
      (node (ref "U10") (pin "5") (pinfunction "OUT_5") (pintype "bidirectional"))
      (node (ref "U9") (pin "7") (pinfunction "LNA_IN_7") (pintype "bidirectional"))
    )
    (net (code "89") (name "Net-(U11-DCC_SW)") (class "Default")
      (node (ref "L20") (pin "2") (pinfunction "2_2") (pintype "passive"))
      (node (ref "U11") (pin "9") (pinfunction "DCC_SW_9") (pintype "bidirectional"))
    )
    (net (code "90") (name "Net-(U11-MOSI)") (class "Default")
      (node (ref "R40") (pin "1") (pinfunction "1_1") (pintype "passive"))
      (node (ref "U11") (pin "17") (pinfunction "MOSI_17") (pintype "bidirectional"))
    )
    (net (code "91") (name "Net-(U11-SCK)") (class "Default")
      (node (ref "R41") (pin "1") (pinfunction "1_1") (pintype "passive"))
      (node (ref "U11") (pin "18") (pinfunction "SCK_18") (pintype "bidirectional"))
    )
    (net (code "92") (name "Net-(U11-VDD_IN)") (class "Default")
      (node (ref "C65") (pin "1") (pinfunction "1_1") (pintype "passive"))
      (node (ref "R36") (pin "2") (pinfunction "2_2") (pintype "passive"))
      (node (ref "U11") (pin "1") (pinfunction "VDD_IN_1") (pintype "bidirectional"))
    )
    (net (code "93") (name "Net-(U11-VREG)") (class "Default")
      (node (ref "C63") (pin "1") (pinfunction "1_1") (pintype "passive"))
      (node (ref "L20") (pin "1") (pinfunction "1_1") (pintype "passive"))
      (node (ref "U11") (pin "7") (pinfunction "VREG_7") (pintype "bidirectional"))
    )
    (net (code "94") (name "Net-(U11-XTA)") (class "Default")
      (node (ref "C66") (pin "1") (pinfunction "1_1") (pintype "passive"))
      (node (ref "U11") (pin "3") (pinfunction "XTA_3") (pintype "bidirectional"))
    )
    (net (code "95") (name "Net-(U13-~{EVENT})") (class "Default")
      (node (ref "R65") (pin "2") (pinfunction "2_2") (pintype "passive"))
      (node (ref "U13") (pin "2") (pinfunction "~{EVENT}_2") (pintype "bidirectional"))
    )
    (net (code "96") (name "Net-(U14-BOOT0)") (class "Default")
      (node (ref "R56") (pin "2") (pinfunction "2_2") (pintype "passive"))
      (node (ref "R57") (pin "1") (pinfunction "1_1") (pintype "passive"))
      (node (ref "U14") (pin "30") (pinfunction "BOOT0_30") (pintype "bidirectional"))
    )
    (net (code "97") (name "Net-(U14-PA4)") (class "Default")
      (node (ref "TP13") (pin "T") (pinfunction "T_T") (pintype "bidirectional"))
      (node (ref "U14") (pin "9") (pinfunction "PA4_9") (pintype "bidirectional"))
    )
    (net (code "98") (name "Net-(U14-PA9)") (class "Default")
      (node (ref "TP12") (pin "T") (pinfunction "T_T") (pintype "bidirectional"))
      (node (ref "U14") (pin "18") (pinfunction "PA9_18") (pintype "bidirectional"))
    )
    (net (code "99") (name "Net-(U14-PA10)") (class "Default")
      (node (ref "TP11") (pin "T") (pinfunction "T_T") (pintype "bidirectional"))
      (node (ref "U14") (pin "19") (pinfunction "PA10_19") (pintype "bidirectional"))
    )
    (net (code "100") (name "Net-(U14-PA11-USB_DM)") (class "Default")
      (node (ref "R66") (pin "2") (pinfunction "2_2") (pintype "passive"))
      (node (ref "U14") (pin "20") (pinfunction "PA11-USB_DM_20") (pintype "bidirectional"))
    )
    (net (code "101") (name "Net-(U14-PA12-USB_DP)") (class "Default")
      (node (ref "R64") (pin "2") (pinfunction "2_2") (pintype "passive"))
      (node (ref "U14") (pin "21") (pinfunction "PA12-USB_DP_21") (pintype "bidirectional"))
    )
    (net (code "102") (name "Net-(U14-PC14-OSC32_IN)") (class "Default")
      (node (ref "C81") (pin "1") (pinfunction "1_1") (pintype "passive"))
      (node (ref "U14") (pin "1") (pinfunction "PC14-OSC32_IN_1") (pintype "bidirectional"))
      (node (ref "X3") (pin "2") (pinfunction "2_2") (pintype "passive"))
    )
    (net (code "103") (name "Net-(U14-PC15-OSC32_OUT)") (class "Default")
      (node (ref "C84") (pin "1") (pinfunction "1_1") (pintype "passive"))
      (node (ref "U14") (pin "2") (pinfunction "PC15-OSC32_OUT_2") (pintype "bidirectional"))
      (node (ref "X3") (pin "1") (pinfunction "1_1") (pintype "passive"))
    )
    (net (code "104") (name "Net-(U14-PD0-OSC_IN)") (class "Default")
      (node (ref "R72") (pin "2") (pinfunction "2_2") (pintype "passive"))
      (node (ref "R73") (pin "2") (pinfunction "2_2") (pintype "passive"))
      (node (ref "U14") (pin "3") (pinfunction "PD0-OSC_IN_3") (pintype "bidirectional"))
    )
    (net (code "105") (name "Net-(X1-ENABLE)") (class "Default")
      (node (ref "R3") (pin "1") (pinfunction "1_1") (pintype "passive"))
      (node (ref "R4") (pin "2") (pinfunction "2_2") (pintype "passive"))
      (node (ref "X1") (pin "1") (pinfunction "ENABLE_1") (pintype "bidirectional"))
    )
    (net (code "106") (name "Net-(X1-VDD)") (class "Default")
      (node (ref "C62") (pin "2") (pinfunction "2_2") (pintype "passive"))
      (node (ref "L4") (pin "1") (pinfunction "1_1") (pintype "bidirectional"))
      (node (ref "R3") (pin "2") (pinfunction "2_2") (pintype "passive"))
      (node (ref "X1") (pin "4") (pinfunction "VDD_4") (pintype "bidirectional"))
    )
    (net (code "107") (name "PPS") (class "Default")
      (node (ref "J1") (pin "19") (pinfunction "19_19") (pintype "bidirectional"))
      (node (ref "TP2") (pin "T") (pinfunction "T_T") (pintype "bidirectional"))
      (node (ref "U1") (pin "8") (pinfunction "PPS_8") (pintype "bidirectional"))
      (node (ref "U14") (pin "27") (pinfunction "PB3_27") (pintype "bidirectional"))
    )
    (net (code "108") (name "RADIO_A_CLK_32M") (class "Default")
      (node (ref "R25") (pin "2") (pinfunction "2_2") (pintype "passive"))
      (node (ref "R72") (pin "1") (pinfunction "1_1") (pintype "passive"))
      (node (ref "U5") (pin "14") (pinfunction "BUSY_14") (pintype "bidirectional"))
    )
    (net (code "109") (name "RADIO_A_CLK_O") (class "Default")
      (node (ref "R28") (pin "2") (pinfunction "2_2") (pintype "passive"))
      (node (ref "U5") (pin "11") (pinfunction "DIO5_11") (pintype "bidirectional"))
    )
    (net (code "110") (name "RADIO_A_CSN") (class "Default")
      (node (ref "U1") (pin "68") (pinfunction "RADIO_A_CSN_68") (pintype "bidirectional"))
      (node (ref "U5") (pin "19") (pinfunction "NSS_19") (pintype "bidirectional"))
    )
    (net (code "111") (name "RADIO_A_IQ_0") (class "Default")
      (node (ref "R26") (pin "2") (pinfunction "2_2") (pintype "passive"))
      (node (ref "U5") (pin "13") (pinfunction "DIO1_13") (pintype "bidirectional"))
    )
    (net (code "112") (name "RADIO_A_IQ_1") (class "Default")
      (node (ref "R27") (pin "2") (pinfunction "2_2") (pintype "passive"))
      (node (ref "U5") (pin "12") (pinfunction "DIO2_12") (pintype "bidirectional"))
    )
    (net (code "113") (name "RADIO_A_IQ_2") (class "Default")
      (node (ref "R29") (pin "2") (pinfunction "2_2") (pintype "passive"))
      (node (ref "U5") (pin "5") (pinfunction "DIO3_5") (pintype "bidirectional"))
    )
    (net (code "114") (name "RADIO_A_IQ_3") (class "Default")
      (node (ref "R24") (pin "2") (pinfunction "2_2") (pintype "passive"))
      (node (ref "U5") (pin "21") (pinfunction "DIO4_21") (pintype "bidirectional"))
    )
    (net (code "115") (name "RADIO_A_RESET") (class "Default")
      (node (ref "U1") (pin "13") (pinfunction "RADIO_CTRL3_13") (pintype "bidirectional"))
      (node (ref "U5") (pin "15") (pinfunction "NRESET_15") (pintype "bidirectional"))
    )
    (net (code "116") (name "RADIO_A_RFIN") (class "Default")
      (node (ref "C6") (pin "2") (pinfunction "2_2") (pintype "passive"))
      (node (ref "L12") (pin "2") (pinfunction "2_2") (pintype "passive"))
      (node (ref "U5") (pin "23") (pinfunction "RFI_N_23") (pintype "bidirectional"))
    )
    (net (code "117") (name "RADIO_A_RFIP") (class "Default")
      (node (ref "C5") (pin "2") (pinfunction "2_2") (pintype "passive"))
      (node (ref "L12") (pin "1") (pinfunction "1_1") (pintype "passive"))
      (node (ref "U5") (pin "22") (pinfunction "RFI_P_22") (pintype "bidirectional"))
    )
    (net (code "118") (name "RADIO_B_CLK_32M") (class "Default")
      (node (ref "R19") (pin "2") (pinfunction "2_2") (pintype "passive"))
      (node (ref "U7") (pin "14") (pinfunction "BUSY_14") (pintype "bidirectional"))
    )
    (net (code "119") (name "RADIO_B_CLK_O") (class "Default")
      (node (ref "R22") (pin "2") (pinfunction "2_2") (pintype "passive"))
      (node (ref "U7") (pin "11") (pinfunction "DIO5_11") (pintype "bidirectional"))
    )
    (net (code "120") (name "RADIO_B_CSN") (class "Default")
      (node (ref "U1") (pin "18") (pinfunction "RADIO_B_CSN_18") (pintype "bidirectional"))
      (node (ref "U7") (pin "19") (pinfunction "NSS_19") (pintype "bidirectional"))
    )
    (net (code "121") (name "RADIO_B_IQ0") (class "Default")
      (node (ref "R20") (pin "2") (pinfunction "2_2") (pintype "passive"))
      (node (ref "U7") (pin "13") (pinfunction "DIO1_13") (pintype "bidirectional"))
    )
    (net (code "122") (name "RADIO_B_IQ_1") (class "Default")
      (node (ref "R21") (pin "2") (pinfunction "2_2") (pintype "passive"))
      (node (ref "U7") (pin "12") (pinfunction "DIO2_12") (pintype "bidirectional"))
    )
    (net (code "123") (name "RADIO_B_IQ_2") (class "Default")
      (node (ref "R23") (pin "2") (pinfunction "2_2") (pintype "passive"))
      (node (ref "U7") (pin "5") (pinfunction "DIO3_5") (pintype "bidirectional"))
    )
    (net (code "124") (name "RADIO_B_IQ_3") (class "Default")
      (node (ref "R18") (pin "2") (pinfunction "2_2") (pintype "passive"))
      (node (ref "U7") (pin "21") (pinfunction "DIO4_21") (pintype "bidirectional"))
    )
    (net (code "125") (name "RADIO_B_RESET") (class "Default")
      (node (ref "U1") (pin "28") (pinfunction "RADIO_CTRL9_28") (pintype "bidirectional"))
      (node (ref "U7") (pin "15") (pinfunction "NRESET_15") (pintype "bidirectional"))
    )
    (net (code "126") (name "RADIO_B_RFIN") (class "Default")
      (node (ref "C10") (pin "2") (pinfunction "2_2") (pintype "passive"))
      (node (ref "L13") (pin "2") (pinfunction "2_2") (pintype "passive"))
      (node (ref "U7") (pin "23") (pinfunction "RFI_N_23") (pintype "bidirectional"))
    )
    (net (code "127") (name "RADIO_B_RFIP") (class "Default")
      (node (ref "C9") (pin "2") (pinfunction "2_2") (pintype "passive"))
      (node (ref "L13") (pin "1") (pinfunction "1_1") (pintype "passive"))
      (node (ref "U7") (pin "22") (pinfunction "RFI_P_22") (pintype "bidirectional"))
    )
    (net (code "128") (name "RESET_PCIE") (class "Default")
      (node (ref "J1") (pin "22") (pinfunction "22_22") (pintype "bidirectional"))
      (node (ref "R59") (pin "2") (pinfunction "2_2") (pintype "passive"))
      (node (ref "R77") (pin "2") (pinfunction "2_2") (pintype "passive"))
    )
    (net (code "129") (name "RFO") (class "Default")
      (node (ref "C53") (pin "1") (pinfunction "1_1") (pintype "passive"))
      (node (ref "L10") (pin "1") (pinfunction "1_1") (pintype "passive"))
      (node (ref "L9") (pin "1") (pinfunction "1_1") (pintype "passive"))
      (node (ref "U5") (pin "24") (pinfunction "RFO_24") (pintype "bidirectional"))
    )
    (net (code "130") (name "RX_ON") (class "Default")
      (node (ref "R32") (pin "1") (pinfunction "1_1") (pintype "passive"))
      (node (ref "U1") (pin "59") (pinfunction "GPIO4_59") (pintype "bidirectional"))
    )
    (net (code "131") (name "SCK") (class "Default")
      (node (ref "R10") (pin "2") (pinfunction "2_2") (pintype "passive"))
      (node (ref "R41") (pin "2") (pinfunction "2_2") (pintype "passive"))
      (node (ref "R49") (pin "1") (pinfunction "1_1") (pintype "passive"))
      (node (ref "R50") (pin "1") (pinfunction "1_1") (pintype "passive"))
    )
    (net (code "132") (name "SCK_A") (class "Default")
      (node (ref "U1") (pin "65") (pinfunction "RADIO_A_SCK_65") (pintype "bidirectional"))
      (node (ref "U5") (pin "18") (pinfunction "SCK_18") (pintype "bidirectional"))
    )
    (net (code "133") (name "SCK_B") (class "Default")
      (node (ref "U1") (pin "21") (pinfunction "RADIO_B_SCK_21") (pintype "bidirectional"))
      (node (ref "U7") (pin "18") (pinfunction "SCK_18") (pintype "bidirectional"))
    )
    (net (code "134") (name "SCLK_PCIE") (class "Default")
      (node (ref "J1") (pin "45") (pinfunction "45_45") (pintype "bidirectional"))
      (node (ref "R49") (pin "2") (pinfunction "2_2") (pintype "passive"))
    )
    (net (code "135") (name "STM32_MISO") (class "Default")
      (node (ref "R45") (pin "2") (pinfunction "2_2") (pintype "passive"))
      (node (ref "U14") (pin "11") (pinfunction "PA6_11") (pintype "bidirectional"))
    )
    (net (code "136") (name "STM32_MOSI") (class "Default")
      (node (ref "R48") (pin "2") (pinfunction "2_2") (pintype "passive"))
      (node (ref "U14") (pin "12") (pinfunction "PA7_12") (pintype "bidirectional"))
    )
    (net (code "137") (name "STM32_SCK") (class "Default")
      (node (ref "R50") (pin "2") (pinfunction "2_2") (pintype "passive"))
      (node (ref "U14") (pin "10") (pinfunction "PA5_10") (pintype "bidirectional"))
    )
    (net (code "138") (name "SWCLK") (class "Default")
      (node (ref "TP7") (pin "T") (pinfunction "T_T") (pintype "bidirectional"))
      (node (ref "U14") (pin "25") (pinfunction "PA14-SWCLK_25") (pintype "bidirectional"))
    )
    (net (code "139") (name "SWDIO") (class "Default")
      (node (ref "TP8") (pin "T") (pinfunction "T_T") (pintype "bidirectional"))
      (node (ref "U14") (pin "22") (pinfunction "PA13-SWDIO_22") (pintype "bidirectional"))
    )
    (net (code "140") (name "SX1261_IO3") (class "Default")
      (node (ref "TP9") (pin "T") (pinfunction "T_T") (pintype "bidirectional"))
      (node (ref "U11") (pin "6") (pinfunction "DIO3_6") (pintype "bidirectional"))
    )
    (net (code "141") (name "SX1261_RFIN") (class "Default")
      (node (ref "C68") (pin "2") (pinfunction "2_2") (pintype "passive"))
      (node (ref "L22") (pin "2") (pinfunction "2_2") (pintype "passive"))
      (node (ref "U11") (pin "22") (pinfunction "RFI_N_22") (pintype "bidirectional"))
    )
    (net (code "142") (name "SX1261_RFIP") (class "Default")
      (node (ref "C73") (pin "1") (pinfunction "1_1") (pintype "passive"))
      (node (ref "L22") (pin "1") (pinfunction "1_1") (pintype "passive"))
      (node (ref "U11") (pin "21") (pinfunction "RFI_P_21") (pintype "bidirectional"))
    )
    (net (code "143") (name "SX1262_BUSY") (class "Default")
      (node (ref "R67") (pin "1") (pinfunction "1_1") (pintype "passive"))
      (node (ref "U11") (pin "14") (pinfunction "BUSY_14") (pintype "bidirectional"))
      (node (ref "U14") (pin "8") (pinfunction "PA0_WKUP_8") (pintype "bidirectional"))
    )
    (net (code "144") (name "SX1262_BUSY_PCIE") (class "Default")
      (node (ref "J1") (pin "8") (pinfunction "8_8") (pintype "bidirectional"))
      (node (ref "R67") (pin "2") (pinfunction "2_2") (pintype "passive"))
    )
    (net (code "145") (name "SX1262_CS") (class "Default")
      (node (ref "R42") (pin "1") (pinfunction "1_1") (pintype "passive"))
      (node (ref "R51") (pin "1") (pinfunction "1_1") (pintype "passive"))
      (node (ref "U11") (pin "19") (pinfunction "NSS_19") (pintype "bidirectional"))
      (node (ref "U14") (pin "29") (pinfunction "PB5_29") (pintype "bidirectional"))
    )
    (net (code "146") (name "SX1262_CS_PCIE") (class "Default")
      (node (ref "J1") (pin "25") (pinfunction "25_25") (pintype "bidirectional"))
      (node (ref "R51") (pin "2") (pinfunction "2_2") (pintype "passive"))
    )
    (net (code "147") (name "SX1262_IO1") (class "Default")
      (node (ref "R61") (pin "1") (pinfunction "1_1") (pintype "passive"))
      (node (ref "U1") (pin "54") (pinfunction "GPIO7_54") (pintype "bidirectional"))
      (node (ref "U11") (pin "13") (pinfunction "DIO1_13") (pintype "bidirectional"))
      (node (ref "U14") (pin "28") (pinfunction "PB4_28") (pintype "bidirectional"))
    )
    (net (code "148") (name "SX1262_IO1_PCIE") (class "Default")
      (node (ref "J1") (pin "33") (pinfunction "33_33") (pintype "bidirectional"))
      (node (ref "R61") (pin "2") (pinfunction "2_2") (pintype "passive"))
    )
    (net (code "149") (name "SX1262_IO2") (class "Default")
      (node (ref "R63") (pin "1") (pinfunction "1_1") (pintype "passive"))
      (node (ref "U11") (pin "12") (pinfunction "DIO2_12") (pintype "bidirectional"))
    )
    (net (code "150") (name "SX1262_IO2_PCIE") (class "Default")
      (node (ref "J1") (pin "31") (pinfunction "31_31") (pintype "bidirectional"))
      (node (ref "R63") (pin "2") (pinfunction "2_2") (pintype "passive"))
    )
    (net (code "151") (name "SX1262_RST") (class "Default")
      (node (ref "R38") (pin "1") (pinfunction "1_1") (pintype "passive"))
      (node (ref "R60") (pin "1") (pinfunction "1_1") (pintype "passive"))
      (node (ref "U11") (pin "15") (pinfunction "NRESET_15") (pintype "bidirectional"))
      (node (ref "U14") (pin "17") (pinfunction "PA8_17") (pintype "bidirectional"))
    )
    (net (code "152") (name "SX1262_RST_PCIE") (class "Default")
      (node (ref "J1") (pin "10") (pinfunction "10_10") (pintype "bidirectional"))
      (node (ref "R60") (pin "2") (pinfunction "2_2") (pintype "passive"))
    )
    (net (code "153") (name "SX1302_GPIO8") (class "Default")
      (node (ref "U1") (pin "53") (pinfunction "GPIO8_53") (pintype "bidirectional"))
      (node (ref "U14") (pin "26") (pinfunction "PA15_26") (pintype "bidirectional"))
    )
    (net (code "154") (name "TX_ON") (class "Default")
      (node (ref "R30") (pin "1") (pinfunction "1_1") (pintype "passive"))
      (node (ref "U1") (pin "63") (pinfunction "GPIO2_63") (pintype "bidirectional"))
    )
    (net (code "155") (name "TX_RX_SW") (class "Default")
      (node (ref "R16") (pin "2") (pinfunction "2_2") (pintype "passive"))
      (node (ref "U1") (pin "12") (pinfunction "RADIO_CTRL2_12") (pintype "bidirectional"))
    )
    (net (code "156") (name "VCCIO") (class "Default")
      (node (ref "C19") (pin "2") (pinfunction "2_2") (pintype "passive"))
      (node (ref "C20") (pin "2") (pinfunction "2_2") (pintype "passive"))
      (node (ref "C25") (pin "2") (pinfunction "2_2") (pintype "passive"))
      (node (ref "C28") (pin "2") (pinfunction "2_2") (pintype "passive"))
      (node (ref "C3") (pin "2") (pinfunction "2_2") (pintype "passive"))
      (node (ref "C41") (pin "2") (pinfunction "2_2") (pintype "passive"))
      (node (ref "C42") (pin "2") (pinfunction "2_2") (pintype "passive"))
      (node (ref "C45") (pin "2") (pinfunction "2_2") (pintype "passive"))
      (node (ref "C47") (pin "2") (pinfunction "2_2") (pintype "passive"))
      (node (ref "C76") (pin "2") (pinfunction "2_2") (pintype "passive"))
      (node (ref "C80") (pin "2") (pinfunction "2_2") (pintype "passive"))
      (node (ref "C83") (pin "2") (pinfunction "2_2") (pintype "passive"))
      (node (ref "C86") (pin "2") (pinfunction "2_2") (pintype "passive"))
      (node (ref "C87") (pin "2") (pinfunction "2_2") (pintype "passive"))
      (node (ref "C88") (pin "2") (pinfunction "2_2") (pintype "passive"))
      (node (ref "C89") (pin "2") (pinfunction "2_2") (pintype "passive"))
      (node (ref "C90") (pin "2") (pinfunction "2_2") (pintype "passive"))
      (node (ref "Q8") (pin "3") (pinfunction "D_3") (pintype "passive"))
      (node (ref "R33") (pin "1") (pinfunction "1_1") (pintype "passive"))
      (node (ref "R34") (pin "2") (pinfunction "2_2") (pintype "passive"))
      (node (ref "R56") (pin "1") (pinfunction "1_1") (pintype "passive"))
      (node (ref "R58") (pin "1") (pinfunction "1_1") (pintype "passive"))
      (node (ref "R65") (pin "1") (pinfunction "1_1") (pintype "passive"))
      (node (ref "R68") (pin "1") (pinfunction "1_1") (pintype "passive"))
      (node (ref "R71") (pin "1") (pinfunction "1_1") (pintype "passive"))
      (node (ref "R80") (pin "2") (pinfunction "2_2") (pintype "passive"))
      (node (ref "TP1") (pin "T") (pinfunction "T_T") (pintype "bidirectional"))
      (node (ref "U1") (pin "14") (pinfunction "VCC_IO_14") (pintype "bidirectional"))
      (node (ref "U1") (pin "30") (pinfunction "VCC_IO_30") (pintype "bidirectional"))
      (node (ref "U1") (pin "47") (pinfunction "VCC_IO_47") (pintype "bidirectional"))
      (node (ref "U1") (pin "61") (pinfunction "VCC_IO_61") (pintype "bidirectional"))
      (node (ref "U13") (pin "3") (pinfunction "VDD_3") (pintype "bidirectional"))
      (node (ref "U14") (pin "24") (pinfunction "VDD_2_24") (pintype "bidirectional"))
      (node (ref "U14") (pin "32") (pinfunction "VDD_3_32") (pintype "bidirectional"))
      (node (ref "U14") (pin "7") (pinfunction "VDDA_7") (pintype "bidirectional"))
    )
    (net (code "157") (name "VCC_1V2") (class "Default")
      (node (ref "C12") (pin "2") (pinfunction "2_2") (pintype "passive"))
      (node (ref "C13") (pin "2") (pinfunction "2_2") (pintype "passive"))
      (node (ref "C23") (pin "2") (pinfunction "2_2") (pintype "passive"))
      (node (ref "C24") (pin "2") (pinfunction "2_2") (pintype "passive"))
      (node (ref "C29") (pin "2") (pinfunction "2_2") (pintype "passive"))
      (node (ref "C40") (pin "2") (pinfunction "2_2") (pintype "passive"))
      (node (ref "C43") (pin "2") (pinfunction "2_2") (pintype "passive"))
      (node (ref "C44") (pin "2") (pinfunction "2_2") (pintype "passive"))
      (node (ref "C71") (pin "2") (pinfunction "2_2") (pintype "passive"))
      (node (ref "C72") (pin "2") (pinfunction "2_2") (pintype "passive"))
      (node (ref "L5") (pin "2") (pinfunction "2_2") (pintype "passive"))
      (node (ref "R79") (pin "1") (pinfunction "1_1") (pintype "passive"))
      (node (ref "R83") (pin "2") (pinfunction "2_2") (pintype "passive"))
      (node (ref "TP14") (pin "T") (pinfunction "T_T") (pintype "bidirectional"))
      (node (ref "U1") (pin "23") (pinfunction "VCC_CORE_23") (pintype "bidirectional"))
      (node (ref "U1") (pin "40") (pinfunction "VCC_CORE_40") (pintype "bidirectional"))
      (node (ref "U1") (pin "5") (pinfunction "VCC_CORE_5") (pintype "bidirectional"))
      (node (ref "U1") (pin "56") (pinfunction "VCC_CORE_56") (pintype "bidirectional"))
      (node (ref "U6") (pin "5") (pinfunction "OUT_5") (pintype "bidirectional"))
    )
    (net (code "158") (name "VCC_FEM") (class "Default")
      (node (ref "C49") (pin "2") (pinfunction "2_2") (pintype "passive"))
      (node (ref "C50") (pin "2") (pinfunction "2_2") (pintype "passive"))
      (node (ref "C51") (pin "2") (pinfunction "2_2") (pintype "passive"))
      (node (ref "C52") (pin "2") (pinfunction "2_2") (pintype "passive"))
      (node (ref "C55") (pin "2") (pinfunction "2_2") (pintype "passive"))
      (node (ref "FB1") (pin "2") (pinfunction "2_2") (pintype "bidirectional"))
      (node (ref "L1") (pin "2") (pinfunction "2_2") (pintype "passive"))
      (node (ref "L2") (pin "2") (pinfunction "2_2") (pintype "passive"))
      (node (ref "U9") (pin "15") (pinfunction "VCC0_15") (pintype "bidirectional"))
    )
    (net (code "159") (name "VCC_RADIO") (class "Default")
      (node (ref "C21") (pin "2") (pinfunction "2_2") (pintype "passive"))
      (node (ref "C22") (pin "2") (pinfunction "2_2") (pintype "passive"))
      (node (ref "C35") (pin "2") (pinfunction "2_2") (pintype "passive"))
      (node (ref "C39") (pin "2") (pinfunction "2_2") (pintype "passive"))
      (node (ref "C48") (pin "2") (pinfunction "2_2") (pintype "passive"))
      (node (ref "C67") (pin "1") (pinfunction "1_1") (pintype "passive"))
      (node (ref "FB3") (pin "2") (pinfunction "2_2") (pintype "bidirectional"))
      (node (ref "L15") (pin "1") (pinfunction "1_1") (pintype "passive"))
      (node (ref "L4") (pin "2") (pinfunction "2_2") (pintype "bidirectional"))
      (node (ref "L7") (pin "1") (pinfunction "1_1") (pintype "passive"))
      (node (ref "R36") (pin "1") (pinfunction "1_1") (pintype "passive"))
      (node (ref "R38") (pin "2") (pinfunction "2_2") (pintype "passive"))
      (node (ref "R42") (pin "2") (pinfunction "2_2") (pintype "passive"))
      (node (ref "TP10") (pin "T") (pinfunction "T_T") (pintype "bidirectional"))
      (node (ref "U11") (pin "10") (pinfunction "VBAT_10") (pintype "bidirectional"))
      (node (ref "U11") (pin "11") (pinfunction "VBAT_IO_11") (pintype "bidirectional"))
      (node (ref "U5") (pin "10") (pinfunction "VBAT_DIO_10") (pintype "bidirectional"))
      (node (ref "U5") (pin "2") (pinfunction "VDD_IN_2") (pintype "bidirectional"))
      (node (ref "U5") (pin "9") (pinfunction "VBAT_RF_9") (pintype "bidirectional"))
      (node (ref "U7") (pin "10") (pinfunction "VBAT_DIO_10") (pintype "bidirectional"))
      (node (ref "U7") (pin "2") (pinfunction "VDD_IN_2") (pintype "bidirectional"))
      (node (ref "U7") (pin "9") (pinfunction "VBAT_RF_9") (pintype "bidirectional"))
    )
    (net (code "160") (name "VIN") (class "Default")
      (node (ref "C30") (pin "2") (pinfunction "2_2") (pintype "passive"))
      (node (ref "C31") (pin "2") (pinfunction "2_2") (pintype "passive"))
      (node (ref "C69") (pin "2") (pinfunction "2_2") (pintype "passive"))
      (node (ref "C70") (pin "2") (pinfunction "2_2") (pintype "passive"))
      (node (ref "FB1") (pin "1") (pinfunction "1_1") (pintype "bidirectional"))
      (node (ref "FB3") (pin "1") (pinfunction "1_1") (pintype "bidirectional"))
      (node (ref "J1") (pin "2") (pinfunction "3V3_2") (pintype "bidirectional"))
      (node (ref "J1") (pin "24") (pinfunction "3V3_24") (pintype "bidirectional"))
      (node (ref "J1") (pin "39") (pinfunction "3V3_39") (pintype "bidirectional"))
      (node (ref "J1") (pin "41") (pinfunction "3V3_41") (pintype "bidirectional"))
      (node (ref "J1") (pin "52") (pinfunction "3V3_52") (pintype "bidirectional"))
      (node (ref "Q8") (pin "2") (pinfunction "S_2") (pintype "passive"))
      (node (ref "R47") (pin "1") (pinfunction "1_1") (pintype "passive"))
      (node (ref "R78") (pin "1") (pinfunction "1_1") (pintype "passive"))
      (node (ref "R82") (pin "1") (pinfunction "1_1") (pintype "passive"))
      (node (ref "TP4") (pin "T") (pinfunction "T_T") (pintype "bidirectional"))
      (node (ref "U6") (pin "2") (pinfunction "VIN_2") (pintype "bidirectional"))
    )
    (net (code "161") (name "unconnected-(J1-1V5-Pad6)") (class "Default")
      (node (ref "J1") (pin "6") (pinfunction "1V5_6") (pintype "bidirectional"))
    )
    (net (code "162") (name "unconnected-(J1-1V5-Pad28)") (class "Default")
      (node (ref "J1") (pin "28") (pinfunction "1V5_28") (pintype "bidirectional"))
    )
    (net (code "163") (name "unconnected-(J1-1V5-Pad48)") (class "Default")
      (node (ref "J1") (pin "48") (pinfunction "1V5_48") (pintype "bidirectional"))
    )
    (net (code "164") (name "unconnected-(J1-Pad1)") (class "Default")
      (node (ref "J1") (pin "1") (pinfunction "1_1") (pintype "bidirectional"))
    )
    (net (code "165") (name "unconnected-(J1-Pad3)") (class "Default")
      (node (ref "J1") (pin "3") (pinfunction "3_3") (pintype "bidirectional"))
    )
    (net (code "166") (name "unconnected-(J1-Pad5)") (class "Default")
      (node (ref "J1") (pin "5") (pinfunction "5_5") (pintype "bidirectional"))
    )
    (net (code "167") (name "unconnected-(J1-Pad7)") (class "Default")
      (node (ref "J1") (pin "7") (pinfunction "7_7") (pintype "bidirectional"))
    )
    (net (code "168") (name "unconnected-(J1-Pad11)") (class "Default")
      (node (ref "J1") (pin "11") (pinfunction "11_11") (pintype "bidirectional"))
    )
    (net (code "169") (name "unconnected-(J1-Pad12)") (class "Default")
      (node (ref "J1") (pin "12") (pinfunction "12_12") (pintype "bidirectional"))
    )
    (net (code "170") (name "unconnected-(J1-Pad13)") (class "Default")
      (node (ref "J1") (pin "13") (pinfunction "13_13") (pintype "bidirectional"))
    )
    (net (code "171") (name "unconnected-(J1-Pad14)") (class "Default")
      (node (ref "J1") (pin "14") (pinfunction "14_14") (pintype "bidirectional"))
    )
    (net (code "172") (name "unconnected-(J1-Pad16)") (class "Default")
      (node (ref "J1") (pin "16") (pinfunction "16_16") (pintype "bidirectional"))
    )
    (net (code "173") (name "unconnected-(J1-Pad17)") (class "Default")
      (node (ref "J1") (pin "17") (pinfunction "17_17") (pintype "bidirectional"))
    )
    (net (code "174") (name "unconnected-(J1-Pad20)") (class "Default")
      (node (ref "J1") (pin "20") (pinfunction "20_20") (pintype "bidirectional"))
    )
    (net (code "175") (name "unconnected-(J1-Pad23)") (class "Default")
      (node (ref "J1") (pin "23") (pinfunction "23_23") (pintype "bidirectional"))
    )
    (net (code "176") (name "unconnected-(J1-Pad42)") (class "Default")
      (node (ref "J1") (pin "42") (pinfunction "42_42") (pintype "bidirectional"))
    )
    (net (code "177") (name "unconnected-(J1-Pad44)") (class "Default")
      (node (ref "J1") (pin "44") (pinfunction "44_44") (pintype "bidirectional"))
    )
    (net (code "178") (name "unconnected-(J1-Pad46)") (class "Default")
      (node (ref "J1") (pin "46") (pinfunction "46_46") (pintype "bidirectional"))
    )
    (net (code "179") (name "unconnected-(U1-GPIO1-Pad64)") (class "Default")
      (node (ref "U1") (pin "64") (pinfunction "GPIO1_64") (pintype "bidirectional"))
    )
    (net (code "180") (name "unconnected-(U1-GPIO3-Pad60)") (class "Default")
      (node (ref "U1") (pin "60") (pinfunction "GPIO3_60") (pintype "bidirectional"))
    )
    (net (code "181") (name "unconnected-(U1-GPIO5-Pad58)") (class "Default")
      (node (ref "U1") (pin "58") (pinfunction "GPIO5_58") (pintype "bidirectional"))
    )
    (net (code "182") (name "unconnected-(U1-GPIO6-Pad57)") (class "Default")
      (node (ref "U1") (pin "57") (pinfunction "GPIO6_57") (pintype "bidirectional"))
    )
    (net (code "183") (name "unconnected-(U1-GPIO9-Pad52)") (class "Default")
      (node (ref "U1") (pin "52") (pinfunction "GPIO9_52") (pintype "bidirectional"))
    )
    (net (code "184") (name "unconnected-(U1-GPIO10-Pad51)") (class "Default")
      (node (ref "U1") (pin "51") (pinfunction "GPIO10_51") (pintype "bidirectional"))
    )
    (net (code "185") (name "unconnected-(U1-GPIO11-Pad50)") (class "Default")
      (node (ref "U1") (pin "50") (pinfunction "GPIO11_50") (pintype "bidirectional"))
    )
    (net (code "186") (name "unconnected-(U1-RADIO_CTRL1-Pad11)") (class "Default")
      (node (ref "U1") (pin "11") (pinfunction "RADIO_CTRL1_11") (pintype "bidirectional"))
    )
    (net (code "187") (name "unconnected-(U1-RADIO_CTRL5-Pad17)") (class "Default")
      (node (ref "U1") (pin "17") (pinfunction "RADIO_CTRL5_17") (pintype "bidirectional"))
    )
    (net (code "188") (name "unconnected-(U1-RADIO_CTRL6-Pad22)") (class "Default")
      (node (ref "U1") (pin "22") (pinfunction "RADIO_CTRL6_22") (pintype "bidirectional"))
    )
    (net (code "189") (name "unconnected-(U1-RADIO_CTRL7-Pad26)") (class "Default")
      (node (ref "U1") (pin "26") (pinfunction "RADIO_CTRL7_26") (pintype "bidirectional"))
    )
    (net (code "190") (name "unconnected-(U1-RADIO_CTRL8-Pad27)") (class "Default")
      (node (ref "U1") (pin "27") (pinfunction "RADIO_CTRL8_27") (pintype "bidirectional"))
    )
    (net (code "191") (name "unconnected-(U1-RADIO_CTRL10-Pad29)") (class "Default")
      (node (ref "U1") (pin "29") (pinfunction "RADIO_CTRL10_29") (pintype "bidirectional"))
    )
    (net (code "192") (name "unconnected-(U1-RADIO_CTRL11-Pad31)") (class "Default")
      (node (ref "U1") (pin "31") (pinfunction "RADIO_CTRL11_31") (pintype "bidirectional"))
    )
    (net (code "193") (name "unconnected-(U5-XTB-Pad4)") (class "Default")
      (node (ref "U5") (pin "4") (pinfunction "XTB_4") (pintype "bidirectional"))
    )
    (net (code "194") (name "unconnected-(U7-RFO-Pad24)") (class "Default")
      (node (ref "U7") (pin "24") (pinfunction "RFO_24") (pintype "bidirectional"))
    )
    (net (code "195") (name "unconnected-(U7-VR_PA-Pad1)") (class "Default")
      (node (ref "U7") (pin "1") (pinfunction "VR_PA_1") (pintype "bidirectional"))
    )
    (net (code "196") (name "unconnected-(U7-XTB-Pad4)") (class "Default")
      (node (ref "U7") (pin "4") (pinfunction "XTB_4") (pintype "bidirectional"))
    )
    (net (code "197") (name "unconnected-(U9-NC-Pad14)") (class "Default")
      (node (ref "U9") (pin "14") (pinfunction "NC_14") (pintype "bidirectional"))
    )
    (net (code "198") (name "unconnected-(U9-TX_ALT-Pad3)") (class "Default")
      (node (ref "U9") (pin "3") (pinfunction "TX_ALT_3") (pintype "bidirectional"))
    )
    (net (code "199") (name "unconnected-(U11-RFO-Pad23)") (class "Default")
      (node (ref "U11") (pin "23") (pinfunction "RFO_23") (pintype "bidirectional"))
    )
    (net (code "200") (name "unconnected-(U11-VR_PA-Pad24)") (class "Default")
      (node (ref "U11") (pin "24") (pinfunction "VR_PA_24") (pintype "bidirectional"))
    )
    (net (code "201") (name "unconnected-(U11-XTB-Pad4)") (class "Default")
      (node (ref "U11") (pin "4") (pinfunction "XTB_4") (pintype "bidirectional"))
    )
    (net (code "202") (name "unconnected-(U14-PD1-OSC_OUT-Pad4)") (class "Default")
      (node (ref "U14") (pin "4") (pinfunction "PD1-OSC_OUT_4") (pintype "bidirectional"))
    )
  )
)
